# Banker_VHDCI_2_EDGE__BUF.net
KiCad netlist of a schematic drawn in Altium Designer
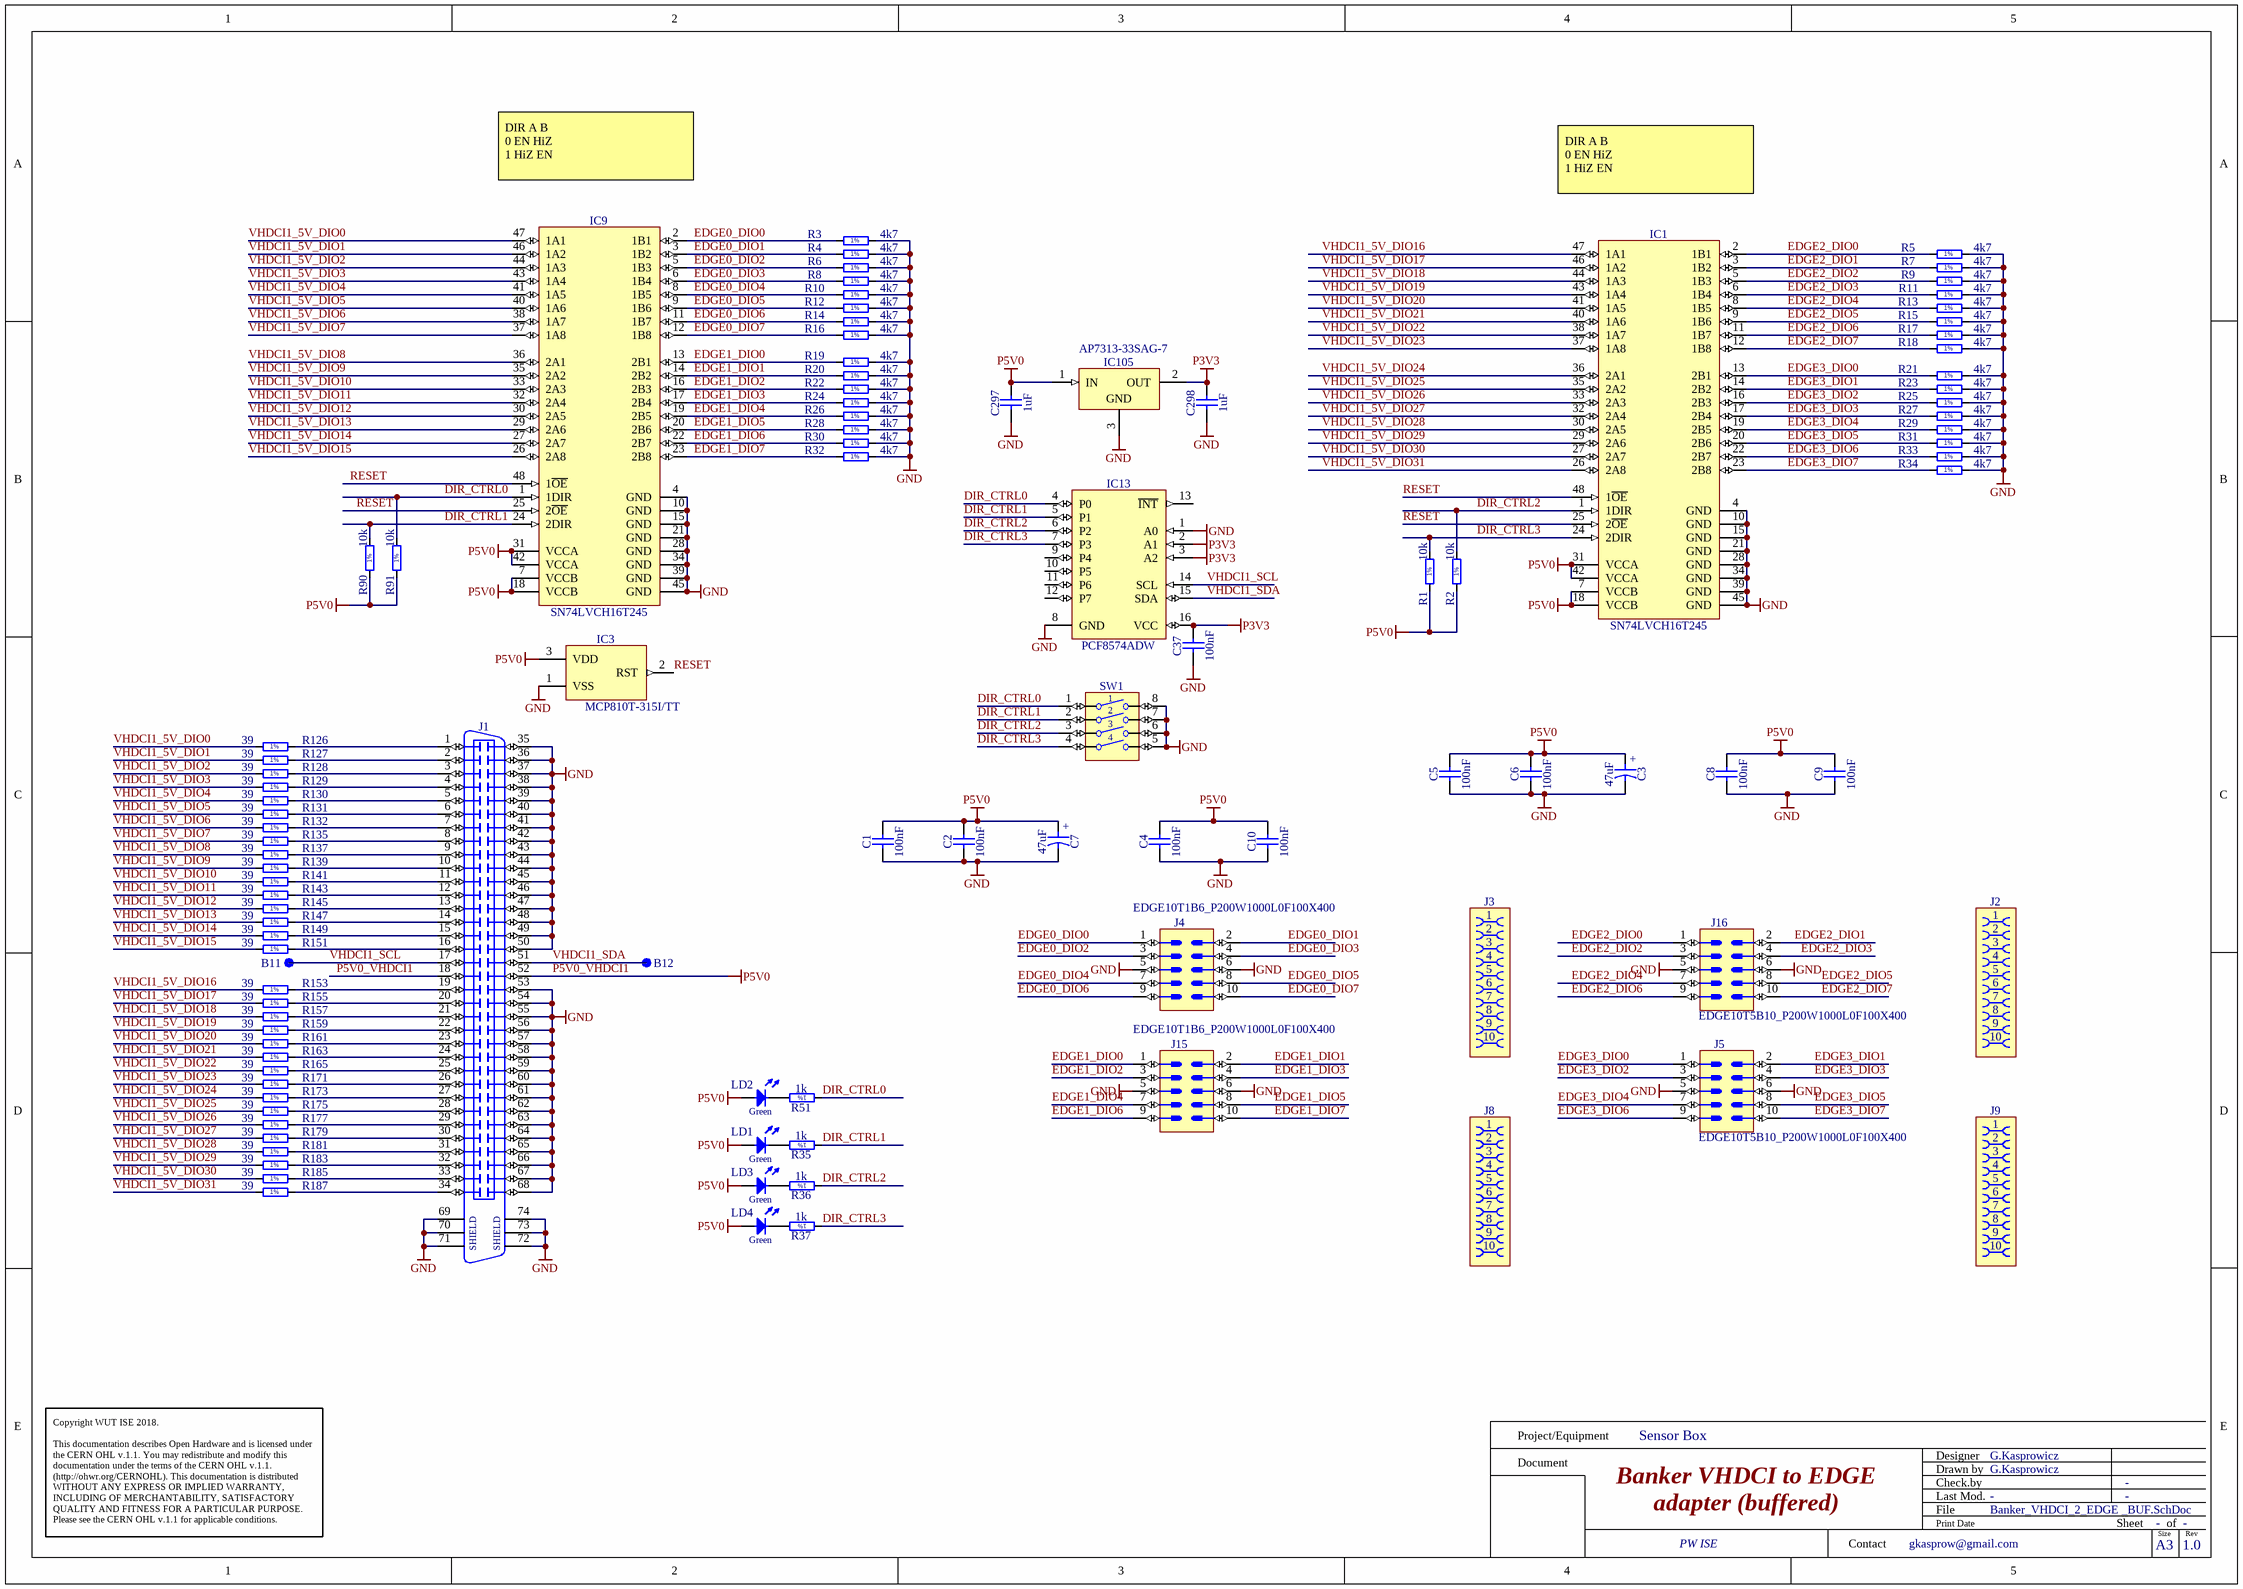
[diagram p0: Banker_VHDCI_2_EDGE _BUF.SchDoc]

(export (version "E")
  (design (tool "Eeschema 10.0.6"))
  (components
    (comp (ref "B11")
      (value "SMD Pad")
      (footprint "C100")
      (description "Through Hole Pad")
      (fields (field (name "PART NUMBER") "SMD_PAD_D1MM") (field (name "AUTHOR") "CERN DEM JLC"))
      (libsource (lib "Eletro-mechanical") (part "Single SMD Pad (Round)"))
    )
    (comp (ref "B12")
      (value "SMD Pad")
      (footprint "C100")
      (description "Through Hole Pad")
      (fields (field (name "PART NUMBER") "SMD_PAD_D1MM") (field (name "AUTHOR") "CERN DEM JLC"))
      (libsource (lib "Eletro-mechanical") (part "Single SMD Pad (Round)"))
    )
    (comp (ref "C1")
      (value "100nF")
      (footprint "CAPC1005X55N")
      (description "Non-polarised capacitor")
      (fields
        (field (name "PART NUMBER") "CC0402_100NF_16V_10%_X5R")
        (field (name "VOLTAGE") "16V")
        (field (name "AUTHOR") "CERN DEM JLC")
      )
      (libsource (lib "Capacitors") (part "Capacitor - non polarized"))
    )
    (comp (ref "C2")
      (value "100nF")
      (footprint "CAPC1005X55N")
      (description "Non-polarised capacitor")
      (fields
        (field (name "PART NUMBER") "CC0402_100NF_16V_10%_X5R")
        (field (name "VOLTAGE") "16V")
        (field (name "AUTHOR") "CERN DEM JLC")
      )
      (libsource (lib "Capacitors") (part "Capacitor - non polarized"))
    )
    (comp (ref "C3")
      (value "47uF")
      (footprint "CAPMP7343X310N")
      (description "Polarised capacitor")
      (fields
        (field (name "PART NUMBER") "CTE7343-31_47UF_25V_10%")
        (field (name "VOLTAGE") "25V")
        (field (name "AUTHOR") "CERN DEM JLC")
      )
      (libsource (lib "Capacitors") (part "Capacitor - polarized"))
    )
    (comp (ref "C4")
      (value "100nF")
      (footprint "CAPC1005X55N")
      (description "Non-polarised capacitor")
      (fields
        (field (name "PART NUMBER") "CC0402_100NF_16V_10%_X5R")
        (field (name "VOLTAGE") "16V")
        (field (name "AUTHOR") "CERN DEM JLC")
      )
      (libsource (lib "Capacitors") (part "Capacitor - non polarized"))
    )
    (comp (ref "C5")
      (value "100nF")
      (footprint "CAPC1005X55N")
      (description "Non-polarised capacitor")
      (fields
        (field (name "PART NUMBER") "CC0402_100NF_16V_10%_X5R")
        (field (name "VOLTAGE") "16V")
        (field (name "AUTHOR") "CERN DEM JLC")
      )
      (libsource (lib "Capacitors") (part "Capacitor - non polarized"))
    )
    (comp (ref "C6")
      (value "100nF")
      (footprint "CAPC1005X55N")
      (description "Non-polarised capacitor")
      (fields
        (field (name "PART NUMBER") "CC0402_100NF_16V_10%_X5R")
        (field (name "VOLTAGE") "16V")
        (field (name "AUTHOR") "CERN DEM JLC")
      )
      (libsource (lib "Capacitors") (part "Capacitor - non polarized"))
    )
    (comp (ref "C7")
      (value "47uF")
      (footprint "CAPMP7343X310N")
      (description "Polarised capacitor")
      (fields
        (field (name "PART NUMBER") "CTE7343-31_47UF_25V_10%")
        (field (name "VOLTAGE") "25V")
        (field (name "AUTHOR") "CERN DEM JLC")
      )
      (libsource (lib "Capacitors") (part "Capacitor - polarized"))
    )
    (comp (ref "C8")
      (value "100nF")
      (footprint "CAPC1005X55N")
      (description "Non-polarised capacitor")
      (fields
        (field (name "PART NUMBER") "CC0402_100NF_16V_10%_X5R")
        (field (name "VOLTAGE") "16V")
        (field (name "AUTHOR") "CERN DEM JLC")
      )
      (libsource (lib "Capacitors") (part "Capacitor - non polarized"))
    )
    (comp (ref "C9")
      (value "100nF")
      (footprint "CAPC1005X55N")
      (description "Non-polarised capacitor")
      (fields
        (field (name "PART NUMBER") "CC0402_100NF_16V_10%_X5R")
        (field (name "VOLTAGE") "16V")
        (field (name "AUTHOR") "CERN DEM JLC")
      )
      (libsource (lib "Capacitors") (part "Capacitor - non polarized"))
    )
    (comp (ref "C10")
      (value "100nF")
      (footprint "CAPC1005X55N")
      (description "Non-polarised capacitor")
      (fields
        (field (name "PART NUMBER") "CC0402_100NF_16V_10%_X5R")
        (field (name "VOLTAGE") "16V")
        (field (name "AUTHOR") "CERN DEM JLC")
      )
      (libsource (lib "Capacitors") (part "Capacitor - non polarized"))
    )
    (comp (ref "C37")
      (value "100nF")
      (footprint "CAPC1005X55N")
      (description "Non-polarised capacitor")
      (fields
        (field (name "PART NUMBER") "CC0402_100NF_16V_10%_X5R")
        (field (name "VOLTAGE") "16V")
        (field (name "AUTHOR") "CERN DEM JLC")
      )
      (libsource (lib "Capacitors") (part "Capacitor - non polarized"))
    )
    (comp (ref "C297")
      (value "1uF")
      (footprint "CAPC1005X55N")
      (description "Non-polarised capacitor")
      (fields
        (field (name "PART NUMBER") "CC0402_1UF_16V_10%_X5R")
        (field (name "VOLTAGE") "16V")
        (field (name "AUTHOR") "CERN DEM JLC")
      )
      (libsource (lib "Capacitors") (part "Capacitor - non polarized"))
    )
    (comp (ref "C298")
      (value "1uF")
      (footprint "CAPC1005X55N")
      (description "Non-polarised capacitor")
      (fields
        (field (name "PART NUMBER") "CC0402_1UF_16V_10%_X5R")
        (field (name "VOLTAGE") "16V")
        (field (name "AUTHOR") "CERN DEM JLC")
      )
      (libsource (lib "Capacitors") (part "Capacitor - non polarized"))
    )
    (comp (ref "IC1")
      (value "SN74LVCH16T245")
      (footprint "SOP50P810X120-48N")
      (description "16-Bit Dual-Supply Bus Transceiver With Configurable Voltage Translation And 3-State Outputs")
      (fields
        (field (name "PART NUMBER") "SN74LVCH16T245DGGR")
        (field (name "MANUFACTURER") "TEXAS INSTRUMENTS")
        (field (name "AUTHOR") "GK")
      )
      (libsource (lib "LIBRARY_SCH") (part "74LVCH16T245"))
    )
    (comp (ref "IC3")
      (value "MCP810T-315I/TT")
      (footprint "SOT95P237X112-3N")
      (description "3.075V Microcontroller Supervisory Circuit With Push-Pull Output")
      (fields (field (name "MANUFACTURER") "MICROCHIP TECHNOLOGY") (field (name "AUTHOR") "GK"))
      (libsource (lib "LIBRARY_SCH") (part "VMON_MCP810"))
    )
    (comp (ref "IC9")
      (value "SN74LVCH16T245")
      (footprint "SOP50P810X120-48N")
      (description "16-Bit Dual-Supply Bus Transceiver With Configurable Voltage Translation And 3-State Outputs")
      (fields
        (field (name "PART NUMBER") "SN74LVCH16T245DGGR")
        (field (name "MANUFACTURER") "TEXAS INSTRUMENTS")
        (field (name "AUTHOR") "GK")
      )
      (libsource (lib "LIBRARY_SCH") (part "74LVCH16T245"))
    )
    (comp (ref "IC13")
      (value "PCF8574ADW")
      (footprint "SOIC127P1030X265-16N")
      (description "Remote 8-bit I/O Expander For I2C Bus")
      (fields (field (name "MANUFACTURER") "TEXAS INSTRUMENTS") (field (name "AUTHOR") "CERN DEM JLC"))
      (libsource (lib "ICs And Semiconductors") (part "PCF8574ADW"))
    )
    (comp (ref "IC105")
      (value "AP7313-33SAG-7")
      (footprint "SOT95P240X130-3N")
      (description "3-Terminal Regulator 1=IN 2=OUT 3=GND")
      (fields (field (name "MANUFACTURER") "DIODES INCORPORATED") (field (name "AUTHOR") "CERN DEM JLC"))
      (libsource (lib "ICs And Semiconductors") (part "REG3 1IN-2OUT-3GND"))
    )
    (comp (ref "J1")
      (value "VHDCI")
      (footprint "MOLEX_73776-0201")
      (description "0.80mm Pitch, 68 Contacts, Ultra+ VHDCI Surface Mount Vertical Receptacle")
      (fields
        (field (name "PART NUMBER") "MOLEX_73776-0201")
        (field (name "MANUFACTURER") "MOLEX")
        (field (name "AUTHOR") "CERN DEM JLC")
      )
      (libsource (lib "Connectors") (part "MOLEX_73776-0201"))
    )
    (comp (ref "J2")
      (value "~")
      (footprint "AVX_00 9159 010 061 916")
      (description "Open Ended Card Edge Connector, 9159 Series")
      (fields
        (field (name "PART NUMBER") "AVX_00 9159 010 061 916")
        (field (name "MANUFACTURER") "AVX")
        (field (name "AUTHOR") "CERN DEM MR")
      )
      (libsource (lib "Connectors") (part "AVX_00 9159 010 061 916"))
    )
    (comp (ref "J3")
      (value "~")
      (footprint "AVX_00 9159 010 061 916")
      (description "Open Ended Card Edge Connector, 9159 Series")
      (fields
        (field (name "PART NUMBER") "AVX_00 9159 010 061 916")
        (field (name "MANUFACTURER") "AVX")
        (field (name "AUTHOR") "CERN DEM MR")
      )
      (libsource (lib "Connectors") (part "AVX_00 9159 010 061 916"))
    )
    (comp (ref "J4")
      (value "~")
      (footprint "EDGE10T1B6_P200W1000L0F100X400")
      (description "PCB Edge Connector 10 (2x5)")
      (fields
        (field (name "PART NUMBER") "EDGE10T1B6_P200W1000L0F100X400")
        (field (name "AUTHOR") "CERN DEM MR")
      )
      (libsource (lib "Connectors") (part "PCB Edge Connector 10 (2x5)"))
    )
    (comp (ref "J5")
      (value "~")
      (footprint "EDGE10T5B10_P200W1000L0F100X400")
      (description "PCB Edge Connector 10 (2x5)")
      (fields
        (field (name "PART NUMBER") "EDGE10T5B10_P200W1000L0F100X400")
        (field (name "AUTHOR") "CERN DEM MR")
      )
      (libsource (lib "Connectors") (part "PCB Edge Connector 10 (2x5)"))
    )
    (comp (ref "J8")
      (value "~")
      (footprint "AVX_00 9159 010 061 916")
      (description "Open Ended Card Edge Connector, 9159 Series")
      (fields
        (field (name "PART NUMBER") "AVX_00 9159 010 061 916")
        (field (name "MANUFACTURER") "AVX")
        (field (name "AUTHOR") "CERN DEM MR")
      )
      (libsource (lib "Connectors") (part "AVX_00 9159 010 061 916"))
    )
    (comp (ref "J9")
      (value "~")
      (footprint "AVX_00 9159 010 061 916")
      (description "Open Ended Card Edge Connector, 9159 Series")
      (fields
        (field (name "PART NUMBER") "AVX_00 9159 010 061 916")
        (field (name "MANUFACTURER") "AVX")
        (field (name "AUTHOR") "CERN DEM MR")
      )
      (libsource (lib "Connectors") (part "AVX_00 9159 010 061 916"))
    )
    (comp (ref "J15")
      (value "~")
      (footprint "EDGE10T1B6_P200W1000L0F100X400")
      (description "PCB Edge Connector 10 (2x5)")
      (fields
        (field (name "PART NUMBER") "EDGE10T1B6_P200W1000L0F100X400")
        (field (name "AUTHOR") "CERN DEM MR")
      )
      (libsource (lib "Connectors") (part "PCB Edge Connector 10 (2x5)"))
    )
    (comp (ref "J16")
      (value "~")
      (footprint "EDGE10T5B10_P200W1000L0F100X400")
      (description "PCB Edge Connector 10 (2x5)")
      (fields
        (field (name "PART NUMBER") "EDGE10T5B10_P200W1000L0F100X400")
        (field (name "AUTHOR") "CERN DEM MR")
      )
      (libsource (lib "Connectors") (part "PCB Edge Connector 10 (2x5)"))
    )
    (comp (ref "LD1")
      (value "Green")
      (footprint "LED_KINGBRIGHT_KPTR3216")
      (description "LED Green 1A 2C")
      (fields
        (field (name "PART NUMBER") "LED_KINGBRIGHT_KPTR-3216CGCK")
        (field (name "MANUFACTURER") "KINGBRIGHT")
        (field (name "AUTHOR") "CERN DEM MR")
      )
      (libsource (lib "ICs And Semiconductors") (part "LED_KINGBRIGHT_KPTR-3216CGCK"))
    )
    (comp (ref "LD2")
      (value "Green")
      (footprint "LED_KINGBRIGHT_KPTR3216")
      (description "LED Green 1A 2C")
      (fields
        (field (name "PART NUMBER") "LED_KINGBRIGHT_KPTR-3216CGCK")
        (field (name "MANUFACTURER") "KINGBRIGHT")
        (field (name "AUTHOR") "CERN DEM MR")
      )
      (libsource (lib "ICs And Semiconductors") (part "LED_KINGBRIGHT_KPTR-3216CGCK"))
    )
    (comp (ref "LD3")
      (value "Green")
      (footprint "LED_KINGBRIGHT_KPTR3216")
      (description "LED Green 1A 2C")
      (fields
        (field (name "PART NUMBER") "LED_KINGBRIGHT_KPTR-3216CGCK")
        (field (name "MANUFACTURER") "KINGBRIGHT")
        (field (name "AUTHOR") "CERN DEM MR")
      )
      (libsource (lib "ICs And Semiconductors") (part "LED_KINGBRIGHT_KPTR-3216CGCK"))
    )
    (comp (ref "LD4")
      (value "Green")
      (footprint "LED_KINGBRIGHT_KPTR3216")
      (description "LED Green 1A 2C")
      (fields
        (field (name "PART NUMBER") "LED_KINGBRIGHT_KPTR-3216CGCK")
        (field (name "MANUFACTURER") "KINGBRIGHT")
        (field (name "AUTHOR") "CERN DEM MR")
      )
      (libsource (lib "ICs And Semiconductors") (part "LED_KINGBRIGHT_KPTR-3216CGCK"))
    )
    (comp (ref "R1")
      (value "10k")
      (footprint "RESC1005X40N")
      (description "Resistor - 1%")
      (fields
        (field (name "PART NUMBER") "R0402_10K_1%_0.0625W_100PPM")
        (field (name "POWER") "0.0625W")
        (field (name "AUTHOR") "CERN DEM JLC")
      )
      (libsource (lib "Resistors") (part "Resistor - 1%"))
    )
    (comp (ref "R2")
      (value "10k")
      (footprint "RESC1005X40N")
      (description "Resistor - 1%")
      (fields
        (field (name "PART NUMBER") "R0402_10K_1%_0.0625W_100PPM")
        (field (name "POWER") "0.0625W")
        (field (name "AUTHOR") "CERN DEM JLC")
      )
      (libsource (lib "Resistors") (part "Resistor - 1%"))
    )
    (comp (ref "R3")
      (value "4k7")
      (footprint "RESC1005X40N")
      (description "Resistor - 1%")
      (fields
        (field (name "PART NUMBER") "R0402_4K7_1%_0.0625W_100PPM")
        (field (name "POWER") "0.0625W")
        (field (name "AUTHOR") "CERN DEM JLC")
      )
      (libsource (lib "Resistors") (part "Resistor - 1%"))
    )
    (comp (ref "R4")
      (value "4k7")
      (footprint "RESC1005X40N")
      (description "Resistor - 1%")
      (fields
        (field (name "PART NUMBER") "R0402_4K7_1%_0.0625W_100PPM")
        (field (name "POWER") "0.0625W")
        (field (name "AUTHOR") "CERN DEM JLC")
      )
      (libsource (lib "Resistors") (part "Resistor - 1%"))
    )
    (comp (ref "R5")
      (value "4k7")
      (footprint "RESC1005X40N")
      (description "Resistor - 1%")
      (fields
        (field (name "PART NUMBER") "R0402_4K7_1%_0.0625W_100PPM")
        (field (name "POWER") "0.0625W")
        (field (name "AUTHOR") "CERN DEM JLC")
      )
      (libsource (lib "Resistors") (part "Resistor - 1%"))
    )
    (comp (ref "R6")
      (value "4k7")
      (footprint "RESC1005X40N")
      (description "Resistor - 1%")
      (fields
        (field (name "PART NUMBER") "R0402_4K7_1%_0.0625W_100PPM")
        (field (name "POWER") "0.0625W")
        (field (name "AUTHOR") "CERN DEM JLC")
      )
      (libsource (lib "Resistors") (part "Resistor - 1%"))
    )
    (comp (ref "R7")
      (value "4k7")
      (footprint "RESC1005X40N")
      (description "Resistor - 1%")
      (fields
        (field (name "PART NUMBER") "R0402_4K7_1%_0.0625W_100PPM")
        (field (name "POWER") "0.0625W")
        (field (name "AUTHOR") "CERN DEM JLC")
      )
      (libsource (lib "Resistors") (part "Resistor - 1%"))
    )
    (comp (ref "R8")
      (value "4k7")
      (footprint "RESC1005X40N")
      (description "Resistor - 1%")
      (fields
        (field (name "PART NUMBER") "R0402_4K7_1%_0.0625W_100PPM")
        (field (name "POWER") "0.0625W")
        (field (name "AUTHOR") "CERN DEM JLC")
      )
      (libsource (lib "Resistors") (part "Resistor - 1%"))
    )
    (comp (ref "R9")
      (value "4k7")
      (footprint "RESC1005X40N")
      (description "Resistor - 1%")
      (fields
        (field (name "PART NUMBER") "R0402_4K7_1%_0.0625W_100PPM")
        (field (name "POWER") "0.0625W")
        (field (name "AUTHOR") "CERN DEM JLC")
      )
      (libsource (lib "Resistors") (part "Resistor - 1%"))
    )
    (comp (ref "R10")
      (value "4k7")
      (footprint "RESC1005X40N")
      (description "Resistor - 1%")
      (fields
        (field (name "PART NUMBER") "R0402_4K7_1%_0.0625W_100PPM")
        (field (name "POWER") "0.0625W")
        (field (name "AUTHOR") "CERN DEM JLC")
      )
      (libsource (lib "Resistors") (part "Resistor - 1%"))
    )
    (comp (ref "R11")
      (value "4k7")
      (footprint "RESC1005X40N")
      (description "Resistor - 1%")
      (fields
        (field (name "PART NUMBER") "R0402_4K7_1%_0.0625W_100PPM")
        (field (name "POWER") "0.0625W")
        (field (name "AUTHOR") "CERN DEM JLC")
      )
      (libsource (lib "Resistors") (part "Resistor - 1%"))
    )
    (comp (ref "R12")
      (value "4k7")
      (footprint "RESC1005X40N")
      (description "Resistor - 1%")
      (fields
        (field (name "PART NUMBER") "R0402_4K7_1%_0.0625W_100PPM")
        (field (name "POWER") "0.0625W")
        (field (name "AUTHOR") "CERN DEM JLC")
      )
      (libsource (lib "Resistors") (part "Resistor - 1%"))
    )
    (comp (ref "R13")
      (value "4k7")
      (footprint "RESC1005X40N")
      (description "Resistor - 1%")
      (fields
        (field (name "PART NUMBER") "R0402_4K7_1%_0.0625W_100PPM")
        (field (name "POWER") "0.0625W")
        (field (name "AUTHOR") "CERN DEM JLC")
      )
      (libsource (lib "Resistors") (part "Resistor - 1%"))
    )
    (comp (ref "R14")
      (value "4k7")
      (footprint "RESC1005X40N")
      (description "Resistor - 1%")
      (fields
        (field (name "PART NUMBER") "R0402_4K7_1%_0.0625W_100PPM")
        (field (name "POWER") "0.0625W")
        (field (name "AUTHOR") "CERN DEM JLC")
      )
      (libsource (lib "Resistors") (part "Resistor - 1%"))
    )
    (comp (ref "R15")
      (value "4k7")
      (footprint "RESC1005X40N")
      (description "Resistor - 1%")
      (fields
        (field (name "PART NUMBER") "R0402_4K7_1%_0.0625W_100PPM")
        (field (name "POWER") "0.0625W")
        (field (name "AUTHOR") "CERN DEM JLC")
      )
      (libsource (lib "Resistors") (part "Resistor - 1%"))
    )
    (comp (ref "R16")
      (value "4k7")
      (footprint "RESC1005X40N")
      (description "Resistor - 1%")
      (fields
        (field (name "PART NUMBER") "R0402_4K7_1%_0.0625W_100PPM")
        (field (name "POWER") "0.0625W")
        (field (name "AUTHOR") "CERN DEM JLC")
      )
      (libsource (lib "Resistors") (part "Resistor - 1%"))
    )
    (comp (ref "R17")
      (value "4k7")
      (footprint "RESC1005X40N")
      (description "Resistor - 1%")
      (fields
        (field (name "PART NUMBER") "R0402_4K7_1%_0.0625W_100PPM")
        (field (name "POWER") "0.0625W")
        (field (name "AUTHOR") "CERN DEM JLC")
      )
      (libsource (lib "Resistors") (part "Resistor - 1%"))
    )
    (comp (ref "R18")
      (value "4k7")
      (footprint "RESC1005X40N")
      (description "Resistor - 1%")
      (fields
        (field (name "PART NUMBER") "R0402_4K7_1%_0.0625W_100PPM")
        (field (name "POWER") "0.0625W")
        (field (name "AUTHOR") "CERN DEM JLC")
      )
      (libsource (lib "Resistors") (part "Resistor - 1%"))
    )
    (comp (ref "R19")
      (value "4k7")
      (footprint "RESC1005X40N")
      (description "Resistor - 1%")
      (fields
        (field (name "PART NUMBER") "R0402_4K7_1%_0.0625W_100PPM")
        (field (name "POWER") "0.0625W")
        (field (name "AUTHOR") "CERN DEM JLC")
      )
      (libsource (lib "Resistors") (part "Resistor - 1%"))
    )
    (comp (ref "R20")
      (value "4k7")
      (footprint "RESC1005X40N")
      (description "Resistor - 1%")
      (fields
        (field (name "PART NUMBER") "R0402_4K7_1%_0.0625W_100PPM")
        (field (name "POWER") "0.0625W")
        (field (name "AUTHOR") "CERN DEM JLC")
      )
      (libsource (lib "Resistors") (part "Resistor - 1%"))
    )
    (comp (ref "R21")
      (value "4k7")
      (footprint "RESC1005X40N")
      (description "Resistor - 1%")
      (fields
        (field (name "PART NUMBER") "R0402_4K7_1%_0.0625W_100PPM")
        (field (name "POWER") "0.0625W")
        (field (name "AUTHOR") "CERN DEM JLC")
      )
      (libsource (lib "Resistors") (part "Resistor - 1%"))
    )
    (comp (ref "R22")
      (value "4k7")
      (footprint "RESC1005X40N")
      (description "Resistor - 1%")
      (fields
        (field (name "PART NUMBER") "R0402_4K7_1%_0.0625W_100PPM")
        (field (name "POWER") "0.0625W")
        (field (name "AUTHOR") "CERN DEM JLC")
      )
      (libsource (lib "Resistors") (part "Resistor - 1%"))
    )
    (comp (ref "R23")
      (value "4k7")
      (footprint "RESC1005X40N")
      (description "Resistor - 1%")
      (fields
        (field (name "PART NUMBER") "R0402_4K7_1%_0.0625W_100PPM")
        (field (name "POWER") "0.0625W")
        (field (name "AUTHOR") "CERN DEM JLC")
      )
      (libsource (lib "Resistors") (part "Resistor - 1%"))
    )
    (comp (ref "R24")
      (value "4k7")
      (footprint "RESC1005X40N")
      (description "Resistor - 1%")
      (fields
        (field (name "PART NUMBER") "R0402_4K7_1%_0.0625W_100PPM")
        (field (name "POWER") "0.0625W")
        (field (name "AUTHOR") "CERN DEM JLC")
      )
      (libsource (lib "Resistors") (part "Resistor - 1%"))
    )
    (comp (ref "R25")
      (value "4k7")
      (footprint "RESC1005X40N")
      (description "Resistor - 1%")
      (fields
        (field (name "PART NUMBER") "R0402_4K7_1%_0.0625W_100PPM")
        (field (name "POWER") "0.0625W")
        (field (name "AUTHOR") "CERN DEM JLC")
      )
      (libsource (lib "Resistors") (part "Resistor - 1%"))
    )
    (comp (ref "R26")
      (value "4k7")
      (footprint "RESC1005X40N")
      (description "Resistor - 1%")
      (fields
        (field (name "PART NUMBER") "R0402_4K7_1%_0.0625W_100PPM")
        (field (name "POWER") "0.0625W")
        (field (name "AUTHOR") "CERN DEM JLC")
      )
      (libsource (lib "Resistors") (part "Resistor - 1%"))
    )
    (comp (ref "R27")
      (value "4k7")
      (footprint "RESC1005X40N")
      (description "Resistor - 1%")
      (fields
        (field (name "PART NUMBER") "R0402_4K7_1%_0.0625W_100PPM")
        (field (name "POWER") "0.0625W")
        (field (name "AUTHOR") "CERN DEM JLC")
      )
      (libsource (lib "Resistors") (part "Resistor - 1%"))
    )
    (comp (ref "R28")
      (value "4k7")
      (footprint "RESC1005X40N")
      (description "Resistor - 1%")
      (fields
        (field (name "PART NUMBER") "R0402_4K7_1%_0.0625W_100PPM")
        (field (name "POWER") "0.0625W")
        (field (name "AUTHOR") "CERN DEM JLC")
      )
      (libsource (lib "Resistors") (part "Resistor - 1%"))
    )
    (comp (ref "R29")
      (value "4k7")
      (footprint "RESC1005X40N")
      (description "Resistor - 1%")
      (fields
        (field (name "PART NUMBER") "R0402_4K7_1%_0.0625W_100PPM")
        (field (name "POWER") "0.0625W")
        (field (name "AUTHOR") "CERN DEM JLC")
      )
      (libsource (lib "Resistors") (part "Resistor - 1%"))
    )
    (comp (ref "R30")
      (value "4k7")
      (footprint "RESC1005X40N")
      (description "Resistor - 1%")
      (fields
        (field (name "PART NUMBER") "R0402_4K7_1%_0.0625W_100PPM")
        (field (name "POWER") "0.0625W")
        (field (name "AUTHOR") "CERN DEM JLC")
      )
      (libsource (lib "Resistors") (part "Resistor - 1%"))
    )
    (comp (ref "R31")
      (value "4k7")
      (footprint "RESC1005X40N")
      (description "Resistor - 1%")
      (fields
        (field (name "PART NUMBER") "R0402_4K7_1%_0.0625W_100PPM")
        (field (name "POWER") "0.0625W")
        (field (name "AUTHOR") "CERN DEM JLC")
      )
      (libsource (lib "Resistors") (part "Resistor - 1%"))
    )
    (comp (ref "R32")
      (value "4k7")
      (footprint "RESC1005X40N")
      (description "Resistor - 1%")
      (fields
        (field (name "PART NUMBER") "R0402_4K7_1%_0.0625W_100PPM")
        (field (name "POWER") "0.0625W")
        (field (name "AUTHOR") "CERN DEM JLC")
      )
      (libsource (lib "Resistors") (part "Resistor - 1%"))
    )
    (comp (ref "R33")
      (value "4k7")
      (footprint "RESC1005X40N")
      (description "Resistor - 1%")
      (fields
        (field (name "PART NUMBER") "R0402_4K7_1%_0.0625W_100PPM")
        (field (name "POWER") "0.0625W")
        (field (name "AUTHOR") "CERN DEM JLC")
      )
      (libsource (lib "Resistors") (part "Resistor - 1%"))
    )
    (comp (ref "R34")
      (value "4k7")
      (footprint "RESC1005X40N")
      (description "Resistor - 1%")
      (fields
        (field (name "PART NUMBER") "R0402_4K7_1%_0.0625W_100PPM")
        (field (name "POWER") "0.0625W")
        (field (name "AUTHOR") "CERN DEM JLC")
      )
      (libsource (lib "Resistors") (part "Resistor - 1%"))
    )
    (comp (ref "R35")
      (value "1k")
      (footprint "RESC1005X40N")
      (description "Resistor - 1%")
      (fields
        (field (name "PART NUMBER") "R0402_1K_1%_0.0625W_100PPM")
        (field (name "POWER") "0.0625W")
        (field (name "AUTHOR") "CERN DEM JLC")
      )
      (libsource (lib "Resistors") (part "Resistor - 1%"))
    )
    (comp (ref "R36")
      (value "1k")
      (footprint "RESC1005X40N")
      (description "Resistor - 1%")
      (fields
        (field (name "PART NUMBER") "R0402_1K_1%_0.0625W_100PPM")
        (field (name "POWER") "0.0625W")
        (field (name "AUTHOR") "CERN DEM JLC")
      )
      (libsource (lib "Resistors") (part "Resistor - 1%"))
    )
    (comp (ref "R37")
      (value "1k")
      (footprint "RESC1005X40N")
      (description "Resistor - 1%")
      (fields
        (field (name "PART NUMBER") "R0402_1K_1%_0.0625W_100PPM")
        (field (name "POWER") "0.0625W")
        (field (name "AUTHOR") "CERN DEM JLC")
      )
      (libsource (lib "Resistors") (part "Resistor - 1%"))
    )
    (comp (ref "R51")
      (value "1k")
      (footprint "RESC1005X40N")
      (description "Resistor - 1%")
      (fields
        (field (name "PART NUMBER") "R0402_1K_1%_0.0625W_100PPM")
        (field (name "POWER") "0.0625W")
        (field (name "AUTHOR") "CERN DEM JLC")
      )
      (libsource (lib "Resistors") (part "Resistor - 1%"))
    )
    (comp (ref "R90")
      (value "10k")
      (footprint "RESC1005X40N")
      (description "Resistor - 1%")
      (fields
        (field (name "PART NUMBER") "R0402_10K_1%_0.0625W_100PPM")
        (field (name "POWER") "0.0625W")
        (field (name "AUTHOR") "CERN DEM JLC")
      )
      (libsource (lib "Resistors") (part "Resistor - 1%"))
    )
    (comp (ref "R91")
      (value "10k")
      (footprint "RESC1005X40N")
      (description "Resistor - 1%")
      (fields
        (field (name "PART NUMBER") "R0402_10K_1%_0.0625W_100PPM")
        (field (name "POWER") "0.0625W")
        (field (name "AUTHOR") "CERN DEM JLC")
      )
      (libsource (lib "Resistors") (part "Resistor - 1%"))
    )
    (comp (ref "R126")
      (value "39")
      (footprint "RESC2012X60N")
      (description "Resistor - 1%")
      (fields
        (field (name "PART NUMBER") "R0805_39R_1%_0.125W_100PPM")
        (field (name "POWER") "0.125W")
        (field (name "AUTHOR") "CERN DEM JLC")
      )
      (libsource (lib "Resistors") (part "Resistor - 1%"))
    )
    (comp (ref "R127")
      (value "39")
      (footprint "RESC2012X60N")
      (description "Resistor - 1%")
      (fields
        (field (name "PART NUMBER") "R0805_39R_1%_0.125W_100PPM")
        (field (name "POWER") "0.125W")
        (field (name "AUTHOR") "CERN DEM JLC")
      )
      (libsource (lib "Resistors") (part "Resistor - 1%"))
    )
    (comp (ref "R128")
      (value "39")
      (footprint "RESC2012X60N")
      (description "Resistor - 1%")
      (fields
        (field (name "PART NUMBER") "R0805_39R_1%_0.125W_100PPM")
        (field (name "POWER") "0.125W")
        (field (name "AUTHOR") "CERN DEM JLC")
      )
      (libsource (lib "Resistors") (part "Resistor - 1%"))
    )
    (comp (ref "R129")
      (value "39")
      (footprint "RESC2012X60N")
      (description "Resistor - 1%")
      (fields
        (field (name "PART NUMBER") "R0805_39R_1%_0.125W_100PPM")
        (field (name "POWER") "0.125W")
        (field (name "AUTHOR") "CERN DEM JLC")
      )
      (libsource (lib "Resistors") (part "Resistor - 1%"))
    )
    (comp (ref "R130")
      (value "39")
      (footprint "RESC2012X60N")
      (description "Resistor - 1%")
      (fields
        (field (name "PART NUMBER") "R0805_39R_1%_0.125W_100PPM")
        (field (name "POWER") "0.125W")
        (field (name "AUTHOR") "CERN DEM JLC")
      )
      (libsource (lib "Resistors") (part "Resistor - 1%"))
    )
    (comp (ref "R131")
      (value "39")
      (footprint "RESC2012X60N")
      (description "Resistor - 1%")
      (fields
        (field (name "PART NUMBER") "R0805_39R_1%_0.125W_100PPM")
        (field (name "POWER") "0.125W")
        (field (name "AUTHOR") "CERN DEM JLC")
      )
      (libsource (lib "Resistors") (part "Resistor - 1%"))
    )
    (comp (ref "R132")
      (value "39")
      (footprint "RESC2012X60N")
      (description "Resistor - 1%")
      (fields
        (field (name "PART NUMBER") "R0805_39R_1%_0.125W_100PPM")
        (field (name "POWER") "0.125W")
        (field (name "AUTHOR") "CERN DEM JLC")
      )
      (libsource (lib "Resistors") (part "Resistor - 1%"))
    )
    (comp (ref "R135")
      (value "39")
      (footprint "RESC2012X60N")
      (description "Resistor - 1%")
      (fields
        (field (name "PART NUMBER") "R0805_39R_1%_0.125W_100PPM")
        (field (name "POWER") "0.125W")
        (field (name "AUTHOR") "CERN DEM JLC")
      )
      (libsource (lib "Resistors") (part "Resistor - 1%"))
    )
    (comp (ref "R137")
      (value "39")
      (footprint "RESC2012X60N")
      (description "Resistor - 1%")
      (fields
        (field (name "PART NUMBER") "R0805_39R_1%_0.125W_100PPM")
        (field (name "POWER") "0.125W")
        (field (name "AUTHOR") "CERN DEM JLC")
      )
      (libsource (lib "Resistors") (part "Resistor - 1%"))
    )
    (comp (ref "R139")
      (value "39")
      (footprint "RESC2012X60N")
      (description "Resistor - 1%")
      (fields
        (field (name "PART NUMBER") "R0805_39R_1%_0.125W_100PPM")
        (field (name "POWER") "0.125W")
        (field (name "AUTHOR") "CERN DEM JLC")
      )
      (libsource (lib "Resistors") (part "Resistor - 1%"))
    )
    (comp (ref "R141")
      (value "39")
      (footprint "RESC2012X60N")
      (description "Resistor - 1%")
      (fields
        (field (name "PART NUMBER") "R0805_39R_1%_0.125W_100PPM")
        (field (name "POWER") "0.125W")
        (field (name "AUTHOR") "CERN DEM JLC")
      )
      (libsource (lib "Resistors") (part "Resistor - 1%"))
    )
    (comp (ref "R143")
      (value "39")
      (footprint "RESC2012X60N")
      (description "Resistor - 1%")
      (fields
        (field (name "PART NUMBER") "R0805_39R_1%_0.125W_100PPM")
        (field (name "POWER") "0.125W")
        (field (name "AUTHOR") "CERN DEM JLC")
      )
      (libsource (lib "Resistors") (part "Resistor - 1%"))
    )
    (comp (ref "R145")
      (value "39")
      (footprint "RESC2012X60N")
      (description "Resistor - 1%")
      (fields
        (field (name "PART NUMBER") "R0805_39R_1%_0.125W_100PPM")
        (field (name "POWER") "0.125W")
        (field (name "AUTHOR") "CERN DEM JLC")
      )
      (libsource (lib "Resistors") (part "Resistor - 1%"))
    )
    (comp (ref "R147")
      (value "39")
      (footprint "RESC2012X60N")
      (description "Resistor - 1%")
      (fields
        (field (name "PART NUMBER") "R0805_39R_1%_0.125W_100PPM")
        (field (name "POWER") "0.125W")
        (field (name "AUTHOR") "CERN DEM JLC")
      )
      (libsource (lib "Resistors") (part "Resistor - 1%"))
    )
    (comp (ref "R149")
      (value "39")
      (footprint "RESC2012X60N")
      (description "Resistor - 1%")
      (fields
        (field (name "PART NUMBER") "R0805_39R_1%_0.125W_100PPM")
        (field (name "POWER") "0.125W")
        (field (name "AUTHOR") "CERN DEM JLC")
      )
      (libsource (lib "Resistors") (part "Resistor - 1%"))
    )
    (comp (ref "R151")
      (value "39")
      (footprint "RESC2012X60N")
      (description "Resistor - 1%")
      (fields
        (field (name "PART NUMBER") "R0805_39R_1%_0.125W_100PPM")
        (field (name "POWER") "0.125W")
        (field (name "AUTHOR") "CERN DEM JLC")
      )
      (libsource (lib "Resistors") (part "Resistor - 1%"))
    )
    (comp (ref "R153")
      (value "39")
      (footprint "RESC2012X60N")
      (description "Resistor - 1%")
      (fields
        (field (name "PART NUMBER") "R0805_39R_1%_0.125W_100PPM")
        (field (name "POWER") "0.125W")
        (field (name "AUTHOR") "CERN DEM JLC")
      )
      (libsource (lib "Resistors") (part "Resistor - 1%"))
    )
    (comp (ref "R155")
      (value "39")
      (footprint "RESC2012X60N")
      (description "Resistor - 1%")
      (fields
        (field (name "PART NUMBER") "R0805_39R_1%_0.125W_100PPM")
        (field (name "POWER") "0.125W")
        (field (name "AUTHOR") "CERN DEM JLC")
      )
      (libsource (lib "Resistors") (part "Resistor - 1%"))
    )
    (comp (ref "R157")
      (value "39")
      (footprint "RESC2012X60N")
      (description "Resistor - 1%")
      (fields
        (field (name "PART NUMBER") "R0805_39R_1%_0.125W_100PPM")
        (field (name "POWER") "0.125W")
        (field (name "AUTHOR") "CERN DEM JLC")
      )
      (libsource (lib "Resistors") (part "Resistor - 1%"))
    )
    (comp (ref "R159")
      (value "39")
      (footprint "RESC2012X60N")
      (description "Resistor - 1%")
      (fields
        (field (name "PART NUMBER") "R0805_39R_1%_0.125W_100PPM")
        (field (name "POWER") "0.125W")
        (field (name "AUTHOR") "CERN DEM JLC")
      )
      (libsource (lib "Resistors") (part "Resistor - 1%"))
    )
    (comp (ref "R161")
      (value "39")
      (footprint "RESC2012X60N")
      (description "Resistor - 1%")
      (fields
        (field (name "PART NUMBER") "R0805_39R_1%_0.125W_100PPM")
        (field (name "POWER") "0.125W")
        (field (name "AUTHOR") "CERN DEM JLC")
      )
      (libsource (lib "Resistors") (part "Resistor - 1%"))
    )
    (comp (ref "R163")
      (value "39")
      (footprint "RESC2012X60N")
      (description "Resistor - 1%")
      (fields
        (field (name "PART NUMBER") "R0805_39R_1%_0.125W_100PPM")
        (field (name "POWER") "0.125W")
        (field (name "AUTHOR") "CERN DEM JLC")
      )
      (libsource (lib "Resistors") (part "Resistor - 1%"))
    )
    (comp (ref "R165")
      (value "39")
      (footprint "RESC2012X60N")
      (description "Resistor - 1%")
      (fields
        (field (name "PART NUMBER") "R0805_39R_1%_0.125W_100PPM")
        (field (name "POWER") "0.125W")
        (field (name "AUTHOR") "CERN DEM JLC")
      )
      (libsource (lib "Resistors") (part "Resistor - 1%"))
    )
    (comp (ref "R171")
      (value "39")
      (footprint "RESC2012X60N")
      (description "Resistor - 1%")
      (fields
        (field (name "PART NUMBER") "R0805_39R_1%_0.125W_100PPM")
        (field (name "POWER") "0.125W")
        (field (name "AUTHOR") "CERN DEM JLC")
      )
      (libsource (lib "Resistors") (part "Resistor - 1%"))
    )
    (comp (ref "R173")
      (value "39")
      (footprint "RESC2012X60N")
      (description "Resistor - 1%")
      (fields
        (field (name "PART NUMBER") "R0805_39R_1%_0.125W_100PPM")
        (field (name "POWER") "0.125W")
        (field (name "AUTHOR") "CERN DEM JLC")
      )
      (libsource (lib "Resistors") (part "Resistor - 1%"))
    )
    (comp (ref "R175")
      (value "39")
      (footprint "RESC2012X60N")
      (description "Resistor - 1%")
      (fields
        (field (name "PART NUMBER") "R0805_39R_1%_0.125W_100PPM")
        (field (name "POWER") "0.125W")
        (field (name "AUTHOR") "CERN DEM JLC")
      )
      (libsource (lib "Resistors") (part "Resistor - 1%"))
    )
    (comp (ref "R177")
      (value "39")
      (footprint "RESC2012X60N")
      (description "Resistor - 1%")
      (fields
        (field (name "PART NUMBER") "R0805_39R_1%_0.125W_100PPM")
        (field (name "POWER") "0.125W")
        (field (name "AUTHOR") "CERN DEM JLC")
      )
      (libsource (lib "Resistors") (part "Resistor - 1%"))
    )
    (comp (ref "R179")
      (value "39")
      (footprint "RESC2012X60N")
      (description "Resistor - 1%")
      (fields
        (field (name "PART NUMBER") "R0805_39R_1%_0.125W_100PPM")
        (field (name "POWER") "0.125W")
        (field (name "AUTHOR") "CERN DEM JLC")
      )
      (libsource (lib "Resistors") (part "Resistor - 1%"))
    )
    (comp (ref "R181")
      (value "39")
      (footprint "RESC2012X60N")
      (description "Resistor - 1%")
      (fields
        (field (name "PART NUMBER") "R0805_39R_1%_0.125W_100PPM")
        (field (name "POWER") "0.125W")
        (field (name "AUTHOR") "CERN DEM JLC")
      )
      (libsource (lib "Resistors") (part "Resistor - 1%"))
    )
    (comp (ref "R183")
      (value "39")
      (footprint "RESC2012X60N")
      (description "Resistor - 1%")
      (fields
        (field (name "PART NUMBER") "R0805_39R_1%_0.125W_100PPM")
        (field (name "POWER") "0.125W")
        (field (name "AUTHOR") "CERN DEM JLC")
      )
      (libsource (lib "Resistors") (part "Resistor - 1%"))
    )
    (comp (ref "R185")
      (value "39")
      (footprint "RESC2012X60N")
      (description "Resistor - 1%")
      (fields
        (field (name "PART NUMBER") "R0805_39R_1%_0.125W_100PPM")
        (field (name "POWER") "0.125W")
        (field (name "AUTHOR") "CERN DEM JLC")
      )
      (libsource (lib "Resistors") (part "Resistor - 1%"))
    )
    (comp (ref "R187")
      (value "39")
      (footprint "RESC2012X60N")
      (description "Resistor - 1%")
      (fields
        (field (name "PART NUMBER") "R0805_39R_1%_0.125W_100PPM")
        (field (name "POWER") "0.125W")
        (field (name "AUTHOR") "CERN DEM JLC")
      )
      (libsource (lib "Resistors") (part "Resistor - 1%"))
    )
    (comp (ref "SW1")
      (value "Switch")
      (footprint "SW_OMRON_A6S-4102-H")
      (description "4 Ways SPST DIP Switch")
      (fields
        (field (name "PART NUMBER") "SW_OMRON_A6S-4102-H")
        (field (name "MANUFACTURER") "OMRON")
        (field (name "AUTHOR") "CERN DEM JMW")
      )
      (libsource (lib "Eletro-mechanical") (part "SW 4x SPST DIP Switch"))
    )
  )
  (nets
    (net (code "1") (name "/DIR_CTRL0") (class "Default")
      (node (ref "IC13") (pin "4") (pinfunction "P0_4") (pintype "bidirectional"))
      (node (ref "IC9") (pin "1") (pinfunction "1DIR_1") (pintype "input"))
      (node (ref "R51") (pin "1") (pinfunction "1_1") (pintype "passive"))
      (node (ref "R91") (pin "2") (pinfunction "2_2") (pintype "passive"))
      (node (ref "SW1") (pin "1") (pinfunction "1_1") (pintype "bidirectional"))
    )
    (net (code "2") (name "/DIR_CTRL1") (class "Default")
      (node (ref "IC13") (pin "5") (pinfunction "P1_5") (pintype "bidirectional"))
      (node (ref "IC9") (pin "24") (pinfunction "2DIR_24") (pintype "input"))
      (node (ref "R35") (pin "1") (pinfunction "1_1") (pintype "passive"))
      (node (ref "R90") (pin "2") (pinfunction "2_2") (pintype "passive"))
      (node (ref "SW1") (pin "2") (pinfunction "2_2") (pintype "bidirectional"))
    )
    (net (code "3") (name "/DIR_CTRL2") (class "Default")
      (node (ref "IC1") (pin "1") (pinfunction "1DIR_1") (pintype "input"))
      (node (ref "IC13") (pin "6") (pinfunction "P2_6") (pintype "bidirectional"))
      (node (ref "R2") (pin "2") (pinfunction "2_2") (pintype "passive"))
      (node (ref "R36") (pin "1") (pinfunction "1_1") (pintype "passive"))
      (node (ref "SW1") (pin "3") (pinfunction "3_3") (pintype "bidirectional"))
    )
    (net (code "4") (name "/DIR_CTRL3") (class "Default")
      (node (ref "IC1") (pin "24") (pinfunction "2DIR_24") (pintype "input"))
      (node (ref "IC13") (pin "7") (pinfunction "P3_7") (pintype "bidirectional"))
      (node (ref "R1") (pin "2") (pinfunction "2_2") (pintype "passive"))
      (node (ref "R37") (pin "1") (pinfunction "1_1") (pintype "passive"))
      (node (ref "SW1") (pin "4") (pinfunction "4_4") (pintype "bidirectional"))
    )
    (net (code "5") (name "/EDGE0_DIO0") (class "Default")
      (node (ref "IC9") (pin "2") (pinfunction "1B1_2") (pintype "bidirectional"))
      (node (ref "J4") (pin "1") (pinfunction "1_1") (pintype "bidirectional"))
      (node (ref "R3") (pin "1") (pinfunction "1_1") (pintype "passive"))
    )
    (net (code "6") (name "/EDGE0_DIO1") (class "Default")
      (node (ref "IC9") (pin "3") (pinfunction "1B2_3") (pintype "bidirectional"))
      (node (ref "J4") (pin "2") (pinfunction "2_2") (pintype "bidirectional"))
      (node (ref "R4") (pin "1") (pinfunction "1_1") (pintype "passive"))
    )
    (net (code "7") (name "/EDGE0_DIO2") (class "Default")
      (node (ref "IC9") (pin "5") (pinfunction "1B3_5") (pintype "bidirectional"))
      (node (ref "J4") (pin "3") (pinfunction "3_3") (pintype "bidirectional"))
      (node (ref "R6") (pin "1") (pinfunction "1_1") (pintype "passive"))
    )
    (net (code "8") (name "/EDGE0_DIO3") (class "Default")
      (node (ref "IC9") (pin "6") (pinfunction "1B4_6") (pintype "bidirectional"))
      (node (ref "J4") (pin "4") (pinfunction "4_4") (pintype "bidirectional"))
      (node (ref "R8") (pin "1") (pinfunction "1_1") (pintype "passive"))
    )
    (net (code "9") (name "/EDGE0_DIO4") (class "Default")
      (node (ref "IC9") (pin "8") (pinfunction "1B5_8") (pintype "bidirectional"))
      (node (ref "J4") (pin "7") (pinfunction "7_7") (pintype "bidirectional"))
      (node (ref "R10") (pin "1") (pinfunction "1_1") (pintype "passive"))
    )
    (net (code "10") (name "/EDGE0_DIO5") (class "Default")
      (node (ref "IC9") (pin "9") (pinfunction "1B6_9") (pintype "bidirectional"))
      (node (ref "J4") (pin "8") (pinfunction "8_8") (pintype "bidirectional"))
      (node (ref "R12") (pin "1") (pinfunction "1_1") (pintype "passive"))
    )
    (net (code "11") (name "/EDGE0_DIO6") (class "Default")
      (node (ref "IC9") (pin "11") (pinfunction "1B7_11") (pintype "bidirectional"))
      (node (ref "J4") (pin "9") (pinfunction "9_9") (pintype "bidirectional"))
      (node (ref "R14") (pin "1") (pinfunction "1_1") (pintype "passive"))
    )
    (net (code "12") (name "/EDGE0_DIO7") (class "Default")
      (node (ref "IC9") (pin "12") (pinfunction "1B8_12") (pintype "bidirectional"))
      (node (ref "J4") (pin "10") (pinfunction "10_10") (pintype "bidirectional"))
      (node (ref "R16") (pin "1") (pinfunction "1_1") (pintype "passive"))
    )
    (net (code "13") (name "/EDGE1_DIO0") (class "Default")
      (node (ref "IC9") (pin "13") (pinfunction "2B1_13") (pintype "bidirectional"))
      (node (ref "J15") (pin "1") (pinfunction "1_1") (pintype "bidirectional"))
      (node (ref "R19") (pin "1") (pinfunction "1_1") (pintype "passive"))
    )
    (net (code "14") (name "/EDGE1_DIO1") (class "Default")
      (node (ref "IC9") (pin "14") (pinfunction "2B2_14") (pintype "bidirectional"))
      (node (ref "J15") (pin "2") (pinfunction "2_2") (pintype "bidirectional"))
      (node (ref "R20") (pin "1") (pinfunction "1_1") (pintype "passive"))
    )
    (net (code "15") (name "/EDGE1_DIO2") (class "Default")
      (node (ref "IC9") (pin "16") (pinfunction "2B3_16") (pintype "bidirectional"))
      (node (ref "J15") (pin "3") (pinfunction "3_3") (pintype "bidirectional"))
      (node (ref "R22") (pin "1") (pinfunction "1_1") (pintype "passive"))
    )
    (net (code "16") (name "/EDGE1_DIO3") (class "Default")
      (node (ref "IC9") (pin "17") (pinfunction "2B4_17") (pintype "bidirectional"))
      (node (ref "J15") (pin "4") (pinfunction "4_4") (pintype "bidirectional"))
      (node (ref "R24") (pin "1") (pinfunction "1_1") (pintype "passive"))
    )
    (net (code "17") (name "/EDGE1_DIO4") (class "Default")
      (node (ref "IC9") (pin "19") (pinfunction "2B5_19") (pintype "bidirectional"))
      (node (ref "J15") (pin "7") (pinfunction "7_7") (pintype "bidirectional"))
      (node (ref "R26") (pin "1") (pinfunction "1_1") (pintype "passive"))
    )
    (net (code "18") (name "/EDGE1_DIO5") (class "Default")
      (node (ref "IC9") (pin "20") (pinfunction "2B6_20") (pintype "bidirectional"))
      (node (ref "J15") (pin "8") (pinfunction "8_8") (pintype "bidirectional"))
      (node (ref "R28") (pin "1") (pinfunction "1_1") (pintype "passive"))
    )
    (net (code "19") (name "/EDGE1_DIO6") (class "Default")
      (node (ref "IC9") (pin "22") (pinfunction "2B7_22") (pintype "bidirectional"))
      (node (ref "J15") (pin "9") (pinfunction "9_9") (pintype "bidirectional"))
      (node (ref "R30") (pin "1") (pinfunction "1_1") (pintype "passive"))
    )
    (net (code "20") (name "/EDGE1_DIO7") (class "Default")
      (node (ref "IC9") (pin "23") (pinfunction "2B8_23") (pintype "bidirectional"))
      (node (ref "J15") (pin "10") (pinfunction "10_10") (pintype "bidirectional"))
      (node (ref "R32") (pin "1") (pinfunction "1_1") (pintype "passive"))
    )
    (net (code "21") (name "/EDGE2_DIO0") (class "Default")
      (node (ref "IC1") (pin "2") (pinfunction "1B1_2") (pintype "bidirectional"))
      (node (ref "J16") (pin "1") (pinfunction "1_1") (pintype "bidirectional"))
      (node (ref "R5") (pin "1") (pinfunction "1_1") (pintype "passive"))
    )
    (net (code "22") (name "/EDGE2_DIO1") (class "Default")
      (node (ref "IC1") (pin "3") (pinfunction "1B2_3") (pintype "bidirectional"))
      (node (ref "J16") (pin "2") (pinfunction "2_2") (pintype "bidirectional"))
      (node (ref "R7") (pin "1") (pinfunction "1_1") (pintype "passive"))
    )
    (net (code "23") (name "/EDGE2_DIO2") (class "Default")
      (node (ref "IC1") (pin "5") (pinfunction "1B3_5") (pintype "bidirectional"))
      (node (ref "J16") (pin "3") (pinfunction "3_3") (pintype "bidirectional"))
      (node (ref "R9") (pin "1") (pinfunction "1_1") (pintype "passive"))
    )
    (net (code "24") (name "/EDGE2_DIO3") (class "Default")
      (node (ref "IC1") (pin "6") (pinfunction "1B4_6") (pintype "bidirectional"))
      (node (ref "J16") (pin "4") (pinfunction "4_4") (pintype "bidirectional"))
      (node (ref "R11") (pin "1") (pinfunction "1_1") (pintype "passive"))
    )
    (net (code "25") (name "/EDGE2_DIO4") (class "Default")
      (node (ref "IC1") (pin "8") (pinfunction "1B5_8") (pintype "bidirectional"))
      (node (ref "J16") (pin "7") (pinfunction "7_7") (pintype "bidirectional"))
      (node (ref "R13") (pin "1") (pinfunction "1_1") (pintype "passive"))
    )
    (net (code "26") (name "/EDGE2_DIO5") (class "Default")
      (node (ref "IC1") (pin "9") (pinfunction "1B6_9") (pintype "bidirectional"))
      (node (ref "J16") (pin "8") (pinfunction "8_8") (pintype "bidirectional"))
      (node (ref "R15") (pin "1") (pinfunction "1_1") (pintype "passive"))
    )
    (net (code "27") (name "/EDGE2_DIO6") (class "Default")
      (node (ref "IC1") (pin "11") (pinfunction "1B7_11") (pintype "bidirectional"))
      (node (ref "J16") (pin "9") (pinfunction "9_9") (pintype "bidirectional"))
      (node (ref "R17") (pin "1") (pinfunction "1_1") (pintype "passive"))
    )
    (net (code "28") (name "/EDGE2_DIO7") (class "Default")
      (node (ref "IC1") (pin "12") (pinfunction "1B8_12") (pintype "bidirectional"))
      (node (ref "J16") (pin "10") (pinfunction "10_10") (pintype "bidirectional"))
      (node (ref "R18") (pin "1") (pinfunction "1_1") (pintype "passive"))
    )
    (net (code "29") (name "/EDGE3_DIO0") (class "Default")
      (node (ref "IC1") (pin "13") (pinfunction "2B1_13") (pintype "bidirectional"))
      (node (ref "J5") (pin "1") (pinfunction "1_1") (pintype "bidirectional"))
      (node (ref "R21") (pin "1") (pinfunction "1_1") (pintype "passive"))
    )
    (net (code "30") (name "/EDGE3_DIO1") (class "Default")
      (node (ref "IC1") (pin "14") (pinfunction "2B2_14") (pintype "bidirectional"))
      (node (ref "J5") (pin "2") (pinfunction "2_2") (pintype "bidirectional"))
      (node (ref "R23") (pin "1") (pinfunction "1_1") (pintype "passive"))
    )
    (net (code "31") (name "/EDGE3_DIO2") (class "Default")
      (node (ref "IC1") (pin "16") (pinfunction "2B3_16") (pintype "bidirectional"))
      (node (ref "J5") (pin "3") (pinfunction "3_3") (pintype "bidirectional"))
      (node (ref "R25") (pin "1") (pinfunction "1_1") (pintype "passive"))
    )
    (net (code "32") (name "/EDGE3_DIO3") (class "Default")
      (node (ref "IC1") (pin "17") (pinfunction "2B4_17") (pintype "bidirectional"))
      (node (ref "J5") (pin "4") (pinfunction "4_4") (pintype "bidirectional"))
      (node (ref "R27") (pin "1") (pinfunction "1_1") (pintype "passive"))
    )
    (net (code "33") (name "/EDGE3_DIO4") (class "Default")
      (node (ref "IC1") (pin "19") (pinfunction "2B5_19") (pintype "bidirectional"))
      (node (ref "J5") (pin "7") (pinfunction "7_7") (pintype "bidirectional"))
      (node (ref "R29") (pin "1") (pinfunction "1_1") (pintype "passive"))
    )
    (net (code "34") (name "/EDGE3_DIO5") (class "Default")
      (node (ref "IC1") (pin "20") (pinfunction "2B6_20") (pintype "bidirectional"))
      (node (ref "J5") (pin "8") (pinfunction "8_8") (pintype "bidirectional"))
      (node (ref "R31") (pin "1") (pinfunction "1_1") (pintype "passive"))
    )
    (net (code "35") (name "/EDGE3_DIO6") (class "Default")
      (node (ref "IC1") (pin "22") (pinfunction "2B7_22") (pintype "bidirectional"))
      (node (ref "J5") (pin "9") (pinfunction "9_9") (pintype "bidirectional"))
      (node (ref "R33") (pin "1") (pinfunction "1_1") (pintype "passive"))
    )
    (net (code "36") (name "/EDGE3_DIO7") (class "Default")
      (node (ref "IC1") (pin "23") (pinfunction "2B8_23") (pintype "bidirectional"))
      (node (ref "J5") (pin "10") (pinfunction "10_10") (pintype "bidirectional"))
      (node (ref "R34") (pin "1") (pinfunction "1_1") (pintype "passive"))
    )
    (net (code "37") (name "/RESET") (class "Default")
      (node (ref "IC1") (pin "25") (pinfunction "2~{OE}_25") (pintype "input"))
      (node (ref "IC1") (pin "48") (pinfunction "1~{OE}_48") (pintype "input"))
      (node (ref "IC3") (pin "2") (pinfunction "RST_2") (pintype "output"))
      (node (ref "IC9") (pin "25") (pinfunction "2~{OE}_25") (pintype "input"))
      (node (ref "IC9") (pin "48") (pinfunction "1~{OE}_48") (pintype "input"))
    )
    (net (code "38") (name "/VHDCI1_5V_DIO0") (class "Default")
      (node (ref "IC9") (pin "47") (pinfunction "1A1_47") (pintype "bidirectional"))
      (node (ref "R126") (pin "1") (pinfunction "1_1") (pintype "passive"))
    )
    (net (code "39") (name "/VHDCI1_5V_DIO1") (class "Default")
      (node (ref "IC9") (pin "46") (pinfunction "1A2_46") (pintype "bidirectional"))
      (node (ref "R127") (pin "1") (pinfunction "1_1") (pintype "passive"))
    )
    (net (code "40") (name "/VHDCI1_5V_DIO2") (class "Default")
      (node (ref "IC9") (pin "44") (pinfunction "1A3_44") (pintype "bidirectional"))
      (node (ref "R128") (pin "1") (pinfunction "1_1") (pintype "passive"))
    )
    (net (code "41") (name "/VHDCI1_5V_DIO3") (class "Default")
      (node (ref "IC9") (pin "43") (pinfunction "1A4_43") (pintype "bidirectional"))
      (node (ref "R129") (pin "1") (pinfunction "1_1") (pintype "passive"))
    )
    (net (code "42") (name "/VHDCI1_5V_DIO4") (class "Default")
      (node (ref "IC9") (pin "41") (pinfunction "1A5_41") (pintype "bidirectional"))
      (node (ref "R130") (pin "1") (pinfunction "1_1") (pintype "passive"))
    )
    (net (code "43") (name "/VHDCI1_5V_DIO5") (class "Default")
      (node (ref "IC9") (pin "40") (pinfunction "1A6_40") (pintype "bidirectional"))
      (node (ref "R131") (pin "1") (pinfunction "1_1") (pintype "passive"))
    )
    (net (code "44") (name "/VHDCI1_5V_DIO6") (class "Default")
      (node (ref "IC9") (pin "38") (pinfunction "1A7_38") (pintype "bidirectional"))
      (node (ref "R132") (pin "1") (pinfunction "1_1") (pintype "passive"))
    )
    (net (code "45") (name "/VHDCI1_5V_DIO7") (class "Default")
      (node (ref "IC9") (pin "37") (pinfunction "1A8_37") (pintype "bidirectional"))
      (node (ref "R135") (pin "1") (pinfunction "1_1") (pintype "passive"))
    )
    (net (code "46") (name "/VHDCI1_5V_DIO8") (class "Default")
      (node (ref "IC9") (pin "36") (pinfunction "2A1_36") (pintype "bidirectional"))
      (node (ref "R137") (pin "1") (pinfunction "1_1") (pintype "passive"))
    )
    (net (code "47") (name "/VHDCI1_5V_DIO9") (class "Default")
      (node (ref "IC9") (pin "35") (pinfunction "2A2_35") (pintype "bidirectional"))
      (node (ref "R139") (pin "1") (pinfunction "1_1") (pintype "passive"))
    )
    (net (code "48") (name "/VHDCI1_5V_DIO10") (class "Default")
      (node (ref "IC9") (pin "33") (pinfunction "2A3_33") (pintype "bidirectional"))
      (node (ref "R141") (pin "1") (pinfunction "1_1") (pintype "passive"))
    )
    (net (code "49") (name "/VHDCI1_5V_DIO11") (class "Default")
      (node (ref "IC9") (pin "32") (pinfunction "2A4_32") (pintype "bidirectional"))
      (node (ref "R143") (pin "1") (pinfunction "1_1") (pintype "passive"))
    )
    (net (code "50") (name "/VHDCI1_5V_DIO12") (class "Default")
      (node (ref "IC9") (pin "30") (pinfunction "2A5_30") (pintype "bidirectional"))
      (node (ref "R145") (pin "1") (pinfunction "1_1") (pintype "passive"))
    )
    (net (code "51") (name "/VHDCI1_5V_DIO13") (class "Default")
      (node (ref "IC9") (pin "29") (pinfunction "2A6_29") (pintype "bidirectional"))
      (node (ref "R147") (pin "1") (pinfunction "1_1") (pintype "passive"))
    )
    (net (code "52") (name "/VHDCI1_5V_DIO14") (class "Default")
      (node (ref "IC9") (pin "27") (pinfunction "2A7_27") (pintype "bidirectional"))
      (node (ref "R149") (pin "1") (pinfunction "1_1") (pintype "passive"))
    )
    (net (code "53") (name "/VHDCI1_5V_DIO15") (class "Default")
      (node (ref "IC9") (pin "26") (pinfunction "2A8_26") (pintype "bidirectional"))
      (node (ref "R151") (pin "1") (pinfunction "1_1") (pintype "passive"))
    )
    (net (code "54") (name "/VHDCI1_5V_DIO16") (class "Default")
      (node (ref "IC1") (pin "47") (pinfunction "1A1_47") (pintype "bidirectional"))
      (node (ref "R153") (pin "1") (pinfunction "1_1") (pintype "passive"))
    )
    (net (code "55") (name "/VHDCI1_5V_DIO17") (class "Default")
      (node (ref "IC1") (pin "46") (pinfunction "1A2_46") (pintype "bidirectional"))
      (node (ref "R155") (pin "1") (pinfunction "1_1") (pintype "passive"))
    )
    (net (code "56") (name "/VHDCI1_5V_DIO18") (class "Default")
      (node (ref "IC1") (pin "44") (pinfunction "1A3_44") (pintype "bidirectional"))
      (node (ref "R157") (pin "1") (pinfunction "1_1") (pintype "passive"))
    )
    (net (code "57") (name "/VHDCI1_5V_DIO19") (class "Default")
      (node (ref "IC1") (pin "43") (pinfunction "1A4_43") (pintype "bidirectional"))
      (node (ref "R159") (pin "1") (pinfunction "1_1") (pintype "passive"))
    )
    (net (code "58") (name "/VHDCI1_5V_DIO20") (class "Default")
      (node (ref "IC1") (pin "41") (pinfunction "1A5_41") (pintype "bidirectional"))
      (node (ref "R161") (pin "1") (pinfunction "1_1") (pintype "passive"))
    )
    (net (code "59") (name "/VHDCI1_5V_DIO21") (class "Default")
      (node (ref "IC1") (pin "40") (pinfunction "1A6_40") (pintype "bidirectional"))
      (node (ref "R163") (pin "1") (pinfunction "1_1") (pintype "passive"))
    )
    (net (code "60") (name "/VHDCI1_5V_DIO22") (class "Default")
      (node (ref "IC1") (pin "38") (pinfunction "1A7_38") (pintype "bidirectional"))
      (node (ref "R165") (pin "1") (pinfunction "1_1") (pintype "passive"))
    )
    (net (code "61") (name "/VHDCI1_5V_DIO23") (class "Default")
      (node (ref "IC1") (pin "37") (pinfunction "1A8_37") (pintype "bidirectional"))
      (node (ref "R171") (pin "1") (pinfunction "1_1") (pintype "passive"))
    )
    (net (code "62") (name "/VHDCI1_5V_DIO24") (class "Default")
      (node (ref "IC1") (pin "36") (pinfunction "2A1_36") (pintype "bidirectional"))
      (node (ref "R173") (pin "1") (pinfunction "1_1") (pintype "passive"))
    )
    (net (code "63") (name "/VHDCI1_5V_DIO25") (class "Default")
      (node (ref "IC1") (pin "35") (pinfunction "2A2_35") (pintype "bidirectional"))
      (node (ref "R175") (pin "1") (pinfunction "1_1") (pintype "passive"))
    )
    (net (code "64") (name "/VHDCI1_5V_DIO26") (class "Default")
      (node (ref "IC1") (pin "33") (pinfunction "2A3_33") (pintype "bidirectional"))
      (node (ref "R177") (pin "1") (pinfunction "1_1") (pintype "passive"))
    )
    (net (code "65") (name "/VHDCI1_5V_DIO27") (class "Default")
      (node (ref "IC1") (pin "32") (pinfunction "2A4_32") (pintype "bidirectional"))
      (node (ref "R179") (pin "1") (pinfunction "1_1") (pintype "passive"))
    )
    (net (code "66") (name "/VHDCI1_5V_DIO28") (class "Default")
      (node (ref "IC1") (pin "30") (pinfunction "2A5_30") (pintype "bidirectional"))
      (node (ref "R181") (pin "1") (pinfunction "1_1") (pintype "passive"))
    )
    (net (code "67") (name "/VHDCI1_5V_DIO29") (class "Default")
      (node (ref "IC1") (pin "29") (pinfunction "2A6_29") (pintype "bidirectional"))
      (node (ref "R183") (pin "1") (pinfunction "1_1") (pintype "passive"))
    )
    (net (code "68") (name "/VHDCI1_5V_DIO30") (class "Default")
      (node (ref "IC1") (pin "27") (pinfunction "2A7_27") (pintype "bidirectional"))
      (node (ref "R185") (pin "1") (pinfunction "1_1") (pintype "passive"))
    )
    (net (code "69") (name "/VHDCI1_5V_DIO31") (class "Default")
      (node (ref "IC1") (pin "26") (pinfunction "2A8_26") (pintype "bidirectional"))
      (node (ref "R187") (pin "1") (pinfunction "1_1") (pintype "passive"))
    )
    (net (code "70") (name "/VHDCI1_SCL") (class "Default")
      (node (ref "B11") (pin "1") (pinfunction "1_1") (pintype "bidirectional"))
      (node (ref "IC13") (pin "14") (pinfunction "SCL_14") (pintype "input"))
      (node (ref "J1") (pin "17") (pinfunction "17_17") (pintype "bidirectional"))
    )
    (net (code "71") (name "/VHDCI1_SDA") (class "Default")
      (node (ref "B12") (pin "1") (pinfunction "1_1") (pintype "bidirectional"))
      (node (ref "IC13") (pin "15") (pinfunction "SDA_15") (pintype "bidirectional"))
      (node (ref "J1") (pin "51") (pinfunction "51_51") (pintype "bidirectional"))
    )
    (net (code "72") (name "GND") (class "Default")
      (node (ref "C1") (pin "1") (pinfunction "1_1") (pintype "passive"))
      (node (ref "C10") (pin "1") (pinfunction "1_1") (pintype "passive"))
      (node (ref "C2") (pin "1") (pinfunction "1_1") (pintype "passive"))
      (node (ref "C297") (pin "1") (pinfunction "1_1") (pintype "passive"))
      (node (ref "C298") (pin "1") (pinfunction "1_1") (pintype "passive"))
      (node (ref "C3") (pin "2") (pinfunction "2_2") (pintype "passive"))
      (node (ref "C37") (pin "1") (pinfunction "1_1") (pintype "passive"))
      (node (ref "C4") (pin "1") (pinfunction "1_1") (pintype "passive"))
      (node (ref "C5") (pin "1") (pinfunction "1_1") (pintype "passive"))
      (node (ref "C6") (pin "1") (pinfunction "1_1") (pintype "passive"))
      (node (ref "C7") (pin "2") (pinfunction "2_2") (pintype "passive"))
      (node (ref "C8") (pin "1") (pinfunction "1_1") (pintype "passive"))
      (node (ref "C9") (pin "1") (pinfunction "1_1") (pintype "passive"))
      (node (ref "IC1") (pin "10") (pinfunction "GND_10") (pintype "power_in"))
      (node (ref "IC1") (pin "15") (pinfunction "GND_15") (pintype "power_in"))
      (node (ref "IC1") (pin "21") (pinfunction "GND_21") (pintype "power_in"))
      (node (ref "IC1") (pin "28") (pinfunction "GND_28") (pintype "power_in"))
      (node (ref "IC1") (pin "34") (pinfunction "GND_34") (pintype "power_in"))
      (node (ref "IC1") (pin "39") (pinfunction "GND_39") (pintype "power_in"))
      (node (ref "IC1") (pin "4") (pinfunction "GND_4") (pintype "power_in"))
      (node (ref "IC1") (pin "45") (pinfunction "GND_45") (pintype "power_in"))
      (node (ref "IC105") (pin "3") (pinfunction "GND_3") (pintype "power_in"))
      (node (ref "IC13") (pin "1") (pinfunction "A0_1") (pintype "input"))
      (node (ref "IC13") (pin "8") (pinfunction "GND_8") (pintype "power_in"))
      (node (ref "IC3") (pin "1") (pinfunction "VSS_1") (pintype "power_in"))
      (node (ref "IC9") (pin "10") (pinfunction "GND_10") (pintype "power_in"))
      (node (ref "IC9") (pin "15") (pinfunction "GND_15") (pintype "power_in"))
      (node (ref "IC9") (pin "21") (pinfunction "GND_21") (pintype "power_in"))
      (node (ref "IC9") (pin "28") (pinfunction "GND_28") (pintype "power_in"))
      (node (ref "IC9") (pin "34") (pinfunction "GND_34") (pintype "power_in"))
      (node (ref "IC9") (pin "39") (pinfunction "GND_39") (pintype "power_in"))
      (node (ref "IC9") (pin "4") (pinfunction "GND_4") (pintype "power_in"))
      (node (ref "IC9") (pin "45") (pinfunction "GND_45") (pintype "power_in"))
      (node (ref "J1") (pin "35") (pinfunction "35_35") (pintype "bidirectional"))
      (node (ref "J1") (pin "36") (pinfunction "36_36") (pintype "bidirectional"))
      (node (ref "J1") (pin "37") (pinfunction "37_37") (pintype "bidirectional"))
      (node (ref "J1") (pin "38") (pinfunction "38_38") (pintype "bidirectional"))
      (node (ref "J1") (pin "39") (pinfunction "39_39") (pintype "bidirectional"))
      (node (ref "J1") (pin "40") (pinfunction "40_40") (pintype "bidirectional"))
      (node (ref "J1") (pin "41") (pinfunction "41_41") (pintype "bidirectional"))
      (node (ref "J1") (pin "42") (pinfunction "42_42") (pintype "bidirectional"))
      (node (ref "J1") (pin "43") (pinfunction "43_43") (pintype "bidirectional"))
      (node (ref "J1") (pin "44") (pinfunction "44_44") (pintype "bidirectional"))
      (node (ref "J1") (pin "45") (pinfunction "45_45") (pintype "bidirectional"))
      (node (ref "J1") (pin "46") (pinfunction "46_46") (pintype "bidirectional"))
      (node (ref "J1") (pin "47") (pinfunction "47_47") (pintype "bidirectional"))
      (node (ref "J1") (pin "48") (pinfunction "48_48") (pintype "bidirectional"))
      (node (ref "J1") (pin "49") (pinfunction "49_49") (pintype "bidirectional"))
      (node (ref "J1") (pin "50") (pinfunction "50_50") (pintype "bidirectional"))
      (node (ref "J1") (pin "53") (pinfunction "53_53") (pintype "bidirectional"))
      (node (ref "J1") (pin "54") (pinfunction "54_54") (pintype "bidirectional"))
      (node (ref "J1") (pin "55") (pinfunction "55_55") (pintype "bidirectional"))
      (node (ref "J1") (pin "56") (pinfunction "56_56") (pintype "bidirectional"))
      (node (ref "J1") (pin "57") (pinfunction "57_57") (pintype "bidirectional"))
      (node (ref "J1") (pin "58") (pinfunction "58_58") (pintype "bidirectional"))
      (node (ref "J1") (pin "59") (pinfunction "59_59") (pintype "bidirectional"))
      (node (ref "J1") (pin "60") (pinfunction "60_60") (pintype "bidirectional"))
      (node (ref "J1") (pin "61") (pinfunction "61_61") (pintype "bidirectional"))
      (node (ref "J1") (pin "62") (pinfunction "62_62") (pintype "bidirectional"))
      (node (ref "J1") (pin "63") (pinfunction "63_63") (pintype "bidirectional"))
      (node (ref "J1") (pin "64") (pinfunction "64_64") (pintype "bidirectional"))
      (node (ref "J1") (pin "65") (pinfunction "65_65") (pintype "bidirectional"))
      (node (ref "J1") (pin "66") (pinfunction "66_66") (pintype "bidirectional"))
      (node (ref "J1") (pin "67") (pinfunction "67_67") (pintype "bidirectional"))
      (node (ref "J1") (pin "68") (pinfunction "68_68") (pintype "bidirectional"))
      (node (ref "J1") (pin "69") (pinfunction "69_69") (pintype "passive"))
      (node (ref "J1") (pin "70") (pinfunction "70_70") (pintype "passive"))
      (node (ref "J1") (pin "71") (pinfunction "71_71") (pintype "passive"))
      (node (ref "J1") (pin "72") (pinfunction "72_72") (pintype "passive"))
      (node (ref "J1") (pin "73") (pinfunction "73_73") (pintype "passive"))
      (node (ref "J1") (pin "74") (pinfunction "74_74") (pintype "passive"))
      (node (ref "J15") (pin "5") (pinfunction "5_5") (pintype "bidirectional"))
      (node (ref "J15") (pin "6") (pinfunction "6_6") (pintype "bidirectional"))
      (node (ref "J16") (pin "5") (pinfunction "5_5") (pintype "bidirectional"))
      (node (ref "J16") (pin "6") (pinfunction "6_6") (pintype "bidirectional"))
      (node (ref "J4") (pin "5") (pinfunction "5_5") (pintype "bidirectional"))
      (node (ref "J4") (pin "6") (pinfunction "6_6") (pintype "bidirectional"))
      (node (ref "J5") (pin "5") (pinfunction "5_5") (pintype "bidirectional"))
      (node (ref "J5") (pin "6") (pinfunction "6_6") (pintype "bidirectional"))
      (node (ref "R10") (pin "2") (pinfunction "2_2") (pintype "passive"))
      (node (ref "R11") (pin "2") (pinfunction "2_2") (pintype "passive"))
      (node (ref "R12") (pin "2") (pinfunction "2_2") (pintype "passive"))
      (node (ref "R13") (pin "2") (pinfunction "2_2") (pintype "passive"))
      (node (ref "R14") (pin "2") (pinfunction "2_2") (pintype "passive"))
      (node (ref "R15") (pin "2") (pinfunction "2_2") (pintype "passive"))
      (node (ref "R16") (pin "2") (pinfunction "2_2") (pintype "passive"))
      (node (ref "R17") (pin "2") (pinfunction "2_2") (pintype "passive"))
      (node (ref "R18") (pin "2") (pinfunction "2_2") (pintype "passive"))
      (node (ref "R19") (pin "2") (pinfunction "2_2") (pintype "passive"))
      (node (ref "R20") (pin "2") (pinfunction "2_2") (pintype "passive"))
      (node (ref "R21") (pin "2") (pinfunction "2_2") (pintype "passive"))
      (node (ref "R22") (pin "2") (pinfunction "2_2") (pintype "passive"))
      (node (ref "R23") (pin "2") (pinfunction "2_2") (pintype "passive"))
      (node (ref "R24") (pin "2") (pinfunction "2_2") (pintype "passive"))
      (node (ref "R25") (pin "2") (pinfunction "2_2") (pintype "passive"))
      (node (ref "R26") (pin "2") (pinfunction "2_2") (pintype "passive"))
      (node (ref "R27") (pin "2") (pinfunction "2_2") (pintype "passive"))
      (node (ref "R28") (pin "2") (pinfunction "2_2") (pintype "passive"))
      (node (ref "R29") (pin "2") (pinfunction "2_2") (pintype "passive"))
      (node (ref "R3") (pin "2") (pinfunction "2_2") (pintype "passive"))
      (node (ref "R30") (pin "2") (pinfunction "2_2") (pintype "passive"))
      (node (ref "R31") (pin "2") (pinfunction "2_2") (pintype "passive"))
      (node (ref "R32") (pin "2") (pinfunction "2_2") (pintype "passive"))
      (node (ref "R33") (pin "2") (pinfunction "2_2") (pintype "passive"))
      (node (ref "R34") (pin "2") (pinfunction "2_2") (pintype "passive"))
      (node (ref "R4") (pin "2") (pinfunction "2_2") (pintype "passive"))
      (node (ref "R5") (pin "2") (pinfunction "2_2") (pintype "passive"))
      (node (ref "R6") (pin "2") (pinfunction "2_2") (pintype "passive"))
      (node (ref "R7") (pin "2") (pinfunction "2_2") (pintype "passive"))
      (node (ref "R8") (pin "2") (pinfunction "2_2") (pintype "passive"))
      (node (ref "R9") (pin "2") (pinfunction "2_2") (pintype "passive"))
      (node (ref "SW1") (pin "5") (pinfunction "5_5") (pintype "bidirectional"))
      (node (ref "SW1") (pin "6") (pinfunction "6_6") (pintype "bidirectional"))
      (node (ref "SW1") (pin "7") (pinfunction "7_7") (pintype "bidirectional"))
      (node (ref "SW1") (pin "8") (pinfunction "8_8") (pintype "bidirectional"))
    )
    (net (code "73") (name "Net-(J1-Pad1)") (class "Default")
      (node (ref "J1") (pin "1") (pinfunction "1_1") (pintype "bidirectional"))
      (node (ref "R126") (pin "2") (pinfunction "2_2") (pintype "passive"))
    )
    (net (code "74") (name "Net-(J1-Pad2)") (class "Default")
      (node (ref "J1") (pin "2") (pinfunction "2_2") (pintype "bidirectional"))
      (node (ref "R127") (pin "2") (pinfunction "2_2") (pintype "passive"))
    )
    (net (code "75") (name "Net-(J1-Pad3)") (class "Default")
      (node (ref "J1") (pin "3") (pinfunction "3_3") (pintype "bidirectional"))
      (node (ref "R128") (pin "2") (pinfunction "2_2") (pintype "passive"))
    )
    (net (code "76") (name "Net-(J1-Pad4)") (class "Default")
      (node (ref "J1") (pin "4") (pinfunction "4_4") (pintype "bidirectional"))
      (node (ref "R129") (pin "2") (pinfunction "2_2") (pintype "passive"))
    )
    (net (code "77") (name "Net-(J1-Pad5)") (class "Default")
      (node (ref "J1") (pin "5") (pinfunction "5_5") (pintype "bidirectional"))
      (node (ref "R130") (pin "2") (pinfunction "2_2") (pintype "passive"))
    )
    (net (code "78") (name "Net-(J1-Pad6)") (class "Default")
      (node (ref "J1") (pin "6") (pinfunction "6_6") (pintype "bidirectional"))
      (node (ref "R131") (pin "2") (pinfunction "2_2") (pintype "passive"))
    )
    (net (code "79") (name "Net-(J1-Pad7)") (class "Default")
      (node (ref "J1") (pin "7") (pinfunction "7_7") (pintype "bidirectional"))
      (node (ref "R132") (pin "2") (pinfunction "2_2") (pintype "passive"))
    )
    (net (code "80") (name "Net-(J1-Pad8)") (class "Default")
      (node (ref "J1") (pin "8") (pinfunction "8_8") (pintype "bidirectional"))
      (node (ref "R135") (pin "2") (pinfunction "2_2") (pintype "passive"))
    )
    (net (code "81") (name "Net-(J1-Pad9)") (class "Default")
      (node (ref "J1") (pin "9") (pinfunction "9_9") (pintype "bidirectional"))
      (node (ref "R137") (pin "2") (pinfunction "2_2") (pintype "passive"))
    )
    (net (code "82") (name "Net-(J1-Pad10)") (class "Default")
      (node (ref "J1") (pin "10") (pinfunction "10_10") (pintype "bidirectional"))
      (node (ref "R139") (pin "2") (pinfunction "2_2") (pintype "passive"))
    )
    (net (code "83") (name "Net-(J1-Pad11)") (class "Default")
      (node (ref "J1") (pin "11") (pinfunction "11_11") (pintype "bidirectional"))
      (node (ref "R141") (pin "2") (pinfunction "2_2") (pintype "passive"))
    )
    (net (code "84") (name "Net-(J1-Pad12)") (class "Default")
      (node (ref "J1") (pin "12") (pinfunction "12_12") (pintype "bidirectional"))
      (node (ref "R143") (pin "2") (pinfunction "2_2") (pintype "passive"))
    )
    (net (code "85") (name "Net-(J1-Pad13)") (class "Default")
      (node (ref "J1") (pin "13") (pinfunction "13_13") (pintype "bidirectional"))
      (node (ref "R145") (pin "2") (pinfunction "2_2") (pintype "passive"))
    )
    (net (code "86") (name "Net-(J1-Pad14)") (class "Default")
      (node (ref "J1") (pin "14") (pinfunction "14_14") (pintype "bidirectional"))
      (node (ref "R147") (pin "2") (pinfunction "2_2") (pintype "passive"))
    )
    (net (code "87") (name "Net-(J1-Pad15)") (class "Default")
      (node (ref "J1") (pin "15") (pinfunction "15_15") (pintype "bidirectional"))
      (node (ref "R149") (pin "2") (pinfunction "2_2") (pintype "passive"))
    )
    (net (code "88") (name "Net-(J1-Pad16)") (class "Default")
      (node (ref "J1") (pin "16") (pinfunction "16_16") (pintype "bidirectional"))
      (node (ref "R151") (pin "2") (pinfunction "2_2") (pintype "passive"))
    )
    (net (code "89") (name "Net-(J1-Pad19)") (class "Default")
      (node (ref "J1") (pin "19") (pinfunction "19_19") (pintype "bidirectional"))
      (node (ref "R153") (pin "2") (pinfunction "2_2") (pintype "passive"))
    )
    (net (code "90") (name "Net-(J1-Pad20)") (class "Default")
      (node (ref "J1") (pin "20") (pinfunction "20_20") (pintype "bidirectional"))
      (node (ref "R155") (pin "2") (pinfunction "2_2") (pintype "passive"))
    )
    (net (code "91") (name "Net-(J1-Pad21)") (class "Default")
      (node (ref "J1") (pin "21") (pinfunction "21_21") (pintype "bidirectional"))
      (node (ref "R157") (pin "2") (pinfunction "2_2") (pintype "passive"))
    )
    (net (code "92") (name "Net-(J1-Pad22)") (class "Default")
      (node (ref "J1") (pin "22") (pinfunction "22_22") (pintype "bidirectional"))
      (node (ref "R159") (pin "2") (pinfunction "2_2") (pintype "passive"))
    )
    (net (code "93") (name "Net-(J1-Pad23)") (class "Default")
      (node (ref "J1") (pin "23") (pinfunction "23_23") (pintype "bidirectional"))
      (node (ref "R161") (pin "2") (pinfunction "2_2") (pintype "passive"))
    )
    (net (code "94") (name "Net-(J1-Pad24)") (class "Default")
      (node (ref "J1") (pin "24") (pinfunction "24_24") (pintype "bidirectional"))
      (node (ref "R163") (pin "2") (pinfunction "2_2") (pintype "passive"))
    )
    (net (code "95") (name "Net-(J1-Pad25)") (class "Default")
      (node (ref "J1") (pin "25") (pinfunction "25_25") (pintype "bidirectional"))
      (node (ref "R165") (pin "2") (pinfunction "2_2") (pintype "passive"))
    )
    (net (code "96") (name "Net-(J1-Pad26)") (class "Default")
      (node (ref "J1") (pin "26") (pinfunction "26_26") (pintype "bidirectional"))
      (node (ref "R171") (pin "2") (pinfunction "2_2") (pintype "passive"))
    )
    (net (code "97") (name "Net-(J1-Pad27)") (class "Default")
      (node (ref "J1") (pin "27") (pinfunction "27_27") (pintype "bidirectional"))
      (node (ref "R173") (pin "2") (pinfunction "2_2") (pintype "passive"))
    )
    (net (code "98") (name "Net-(J1-Pad28)") (class "Default")
      (node (ref "J1") (pin "28") (pinfunction "28_28") (pintype "bidirectional"))
      (node (ref "R175") (pin "2") (pinfunction "2_2") (pintype "passive"))
    )
    (net (code "99") (name "Net-(J1-Pad29)") (class "Default")
      (node (ref "J1") (pin "29") (pinfunction "29_29") (pintype "bidirectional"))
      (node (ref "R177") (pin "2") (pinfunction "2_2") (pintype "passive"))
    )
    (net (code "100") (name "Net-(J1-Pad30)") (class "Default")
      (node (ref "J1") (pin "30") (pinfunction "30_30") (pintype "bidirectional"))
      (node (ref "R179") (pin "2") (pinfunction "2_2") (pintype "passive"))
    )
    (net (code "101") (name "Net-(J1-Pad31)") (class "Default")
      (node (ref "J1") (pin "31") (pinfunction "31_31") (pintype "bidirectional"))
      (node (ref "R181") (pin "2") (pinfunction "2_2") (pintype "passive"))
    )
    (net (code "102") (name "Net-(J1-Pad32)") (class "Default")
      (node (ref "J1") (pin "32") (pinfunction "32_32") (pintype "bidirectional"))
      (node (ref "R183") (pin "2") (pinfunction "2_2") (pintype "passive"))
    )
    (net (code "103") (name "Net-(J1-Pad33)") (class "Default")
      (node (ref "J1") (pin "33") (pinfunction "33_33") (pintype "bidirectional"))
      (node (ref "R185") (pin "2") (pinfunction "2_2") (pintype "passive"))
    )
    (net (code "104") (name "Net-(J1-Pad34)") (class "Default")
      (node (ref "J1") (pin "34") (pinfunction "34_34") (pintype "bidirectional"))
      (node (ref "R187") (pin "2") (pinfunction "2_2") (pintype "passive"))
    )
    (net (code "105") (name "Net-(LD1-C)") (class "Default")
      (node (ref "LD1") (pin "1") (pinfunction "C_1") (pintype "passive"))
      (node (ref "R35") (pin "2") (pinfunction "2_2") (pintype "passive"))
    )
    (net (code "106") (name "Net-(LD2-C)") (class "Default")
      (node (ref "LD2") (pin "1") (pinfunction "C_1") (pintype "passive"))
      (node (ref "R51") (pin "2") (pinfunction "2_2") (pintype "passive"))
    )
    (net (code "107") (name "Net-(LD3-C)") (class "Default")
      (node (ref "LD3") (pin "1") (pinfunction "C_1") (pintype "passive"))
      (node (ref "R36") (pin "2") (pinfunction "2_2") (pintype "passive"))
    )
    (net (code "108") (name "Net-(LD4-C)") (class "Default")
      (node (ref "LD4") (pin "1") (pinfunction "C_1") (pintype "passive"))
      (node (ref "R37") (pin "2") (pinfunction "2_2") (pintype "passive"))
    )
    (net (code "109") (name "P3V3") (class "Default")
      (node (ref "C298") (pin "2") (pinfunction "2_2") (pintype "passive"))
      (node (ref "C37") (pin "2") (pinfunction "2_2") (pintype "passive"))
      (node (ref "IC105") (pin "2") (pinfunction "OUT_2") (pintype "power_in"))
      (node (ref "IC13") (pin "16") (pinfunction "VCC_16") (pintype "bidirectional"))
      (node (ref "IC13") (pin "2") (pinfunction "A1_2") (pintype "input"))
      (node (ref "IC13") (pin "3") (pinfunction "A2_3") (pintype "input"))
    )
    (net (code "110") (name "P5V0") (class "Default")
      (node (ref "C1") (pin "2") (pinfunction "2_2") (pintype "passive"))
      (node (ref "C10") (pin "2") (pinfunction "2_2") (pintype "passive"))
      (node (ref "C2") (pin "2") (pinfunction "2_2") (pintype "passive"))
      (node (ref "C297") (pin "2") (pinfunction "2_2") (pintype "passive"))
      (node (ref "C3") (pin "1") (pinfunction "1_1") (pintype "passive"))
      (node (ref "C4") (pin "2") (pinfunction "2_2") (pintype "passive"))
      (node (ref "C5") (pin "2") (pinfunction "2_2") (pintype "passive"))
      (node (ref "C6") (pin "2") (pinfunction "2_2") (pintype "passive"))
      (node (ref "C7") (pin "1") (pinfunction "1_1") (pintype "passive"))
      (node (ref "C8") (pin "2") (pinfunction "2_2") (pintype "passive"))
      (node (ref "C9") (pin "2") (pinfunction "2_2") (pintype "passive"))
      (node (ref "IC1") (pin "18") (pinfunction "VCCB_18") (pintype "power_in"))
      (node (ref "IC1") (pin "31") (pinfunction "VCCA_31") (pintype "power_in"))
      (node (ref "IC1") (pin "42") (pinfunction "VCCA_42") (pintype "power_in"))
      (node (ref "IC1") (pin "7") (pinfunction "VCCB_7") (pintype "power_in"))
      (node (ref "IC105") (pin "1") (pinfunction "IN_1") (pintype "input"))
      (node (ref "IC3") (pin "3") (pinfunction "VDD_3") (pintype "power_in"))
      (node (ref "IC9") (pin "18") (pinfunction "VCCB_18") (pintype "power_in"))
      (node (ref "IC9") (pin "31") (pinfunction "VCCA_31") (pintype "power_in"))
      (node (ref "IC9") (pin "42") (pinfunction "VCCA_42") (pintype "power_in"))
      (node (ref "IC9") (pin "7") (pinfunction "VCCB_7") (pintype "power_in"))
      (node (ref "J1") (pin "18") (pinfunction "18_18") (pintype "bidirectional"))
      (node (ref "J1") (pin "52") (pinfunction "52_52") (pintype "bidirectional"))
      (node (ref "LD1") (pin "2") (pinfunction "A_2") (pintype "passive"))
      (node (ref "LD2") (pin "2") (pinfunction "A_2") (pintype "passive"))
      (node (ref "LD3") (pin "2") (pinfunction "A_2") (pintype "passive"))
      (node (ref "LD4") (pin "2") (pinfunction "A_2") (pintype "passive"))
      (node (ref "R1") (pin "1") (pinfunction "1_1") (pintype "passive"))
      (node (ref "R2") (pin "1") (pinfunction "1_1") (pintype "passive"))
      (node (ref "R90") (pin "1") (pinfunction "1_1") (pintype "passive"))
      (node (ref "R91") (pin "1") (pinfunction "1_1") (pintype "passive"))
    )
    (net (code "111") (name "unconnected-(IC13-P4-Pad9)") (class "Default")
      (node (ref "IC13") (pin "9") (pinfunction "P4_9") (pintype "bidirectional"))
    )
    (net (code "112") (name "unconnected-(IC13-P5-Pad10)") (class "Default")
      (node (ref "IC13") (pin "10") (pinfunction "P5_10") (pintype "bidirectional"))
    )
    (net (code "113") (name "unconnected-(IC13-P6-Pad11)") (class "Default")
      (node (ref "IC13") (pin "11") (pinfunction "P6_11") (pintype "bidirectional"))
    )
    (net (code "114") (name "unconnected-(IC13-P7-Pad12)") (class "Default")
      (node (ref "IC13") (pin "12") (pinfunction "P7_12") (pintype "bidirectional"))
    )
    (net (code "115") (name "unconnected-(IC13-~{INT}-Pad13)") (class "Default")
      (node (ref "IC13") (pin "13") (pinfunction "~{INT}_13") (pintype "output"))
    )
  )
)
